# Precision_Dual_Layer.net
KiCad netlist of a schematic drawn in EAGLE
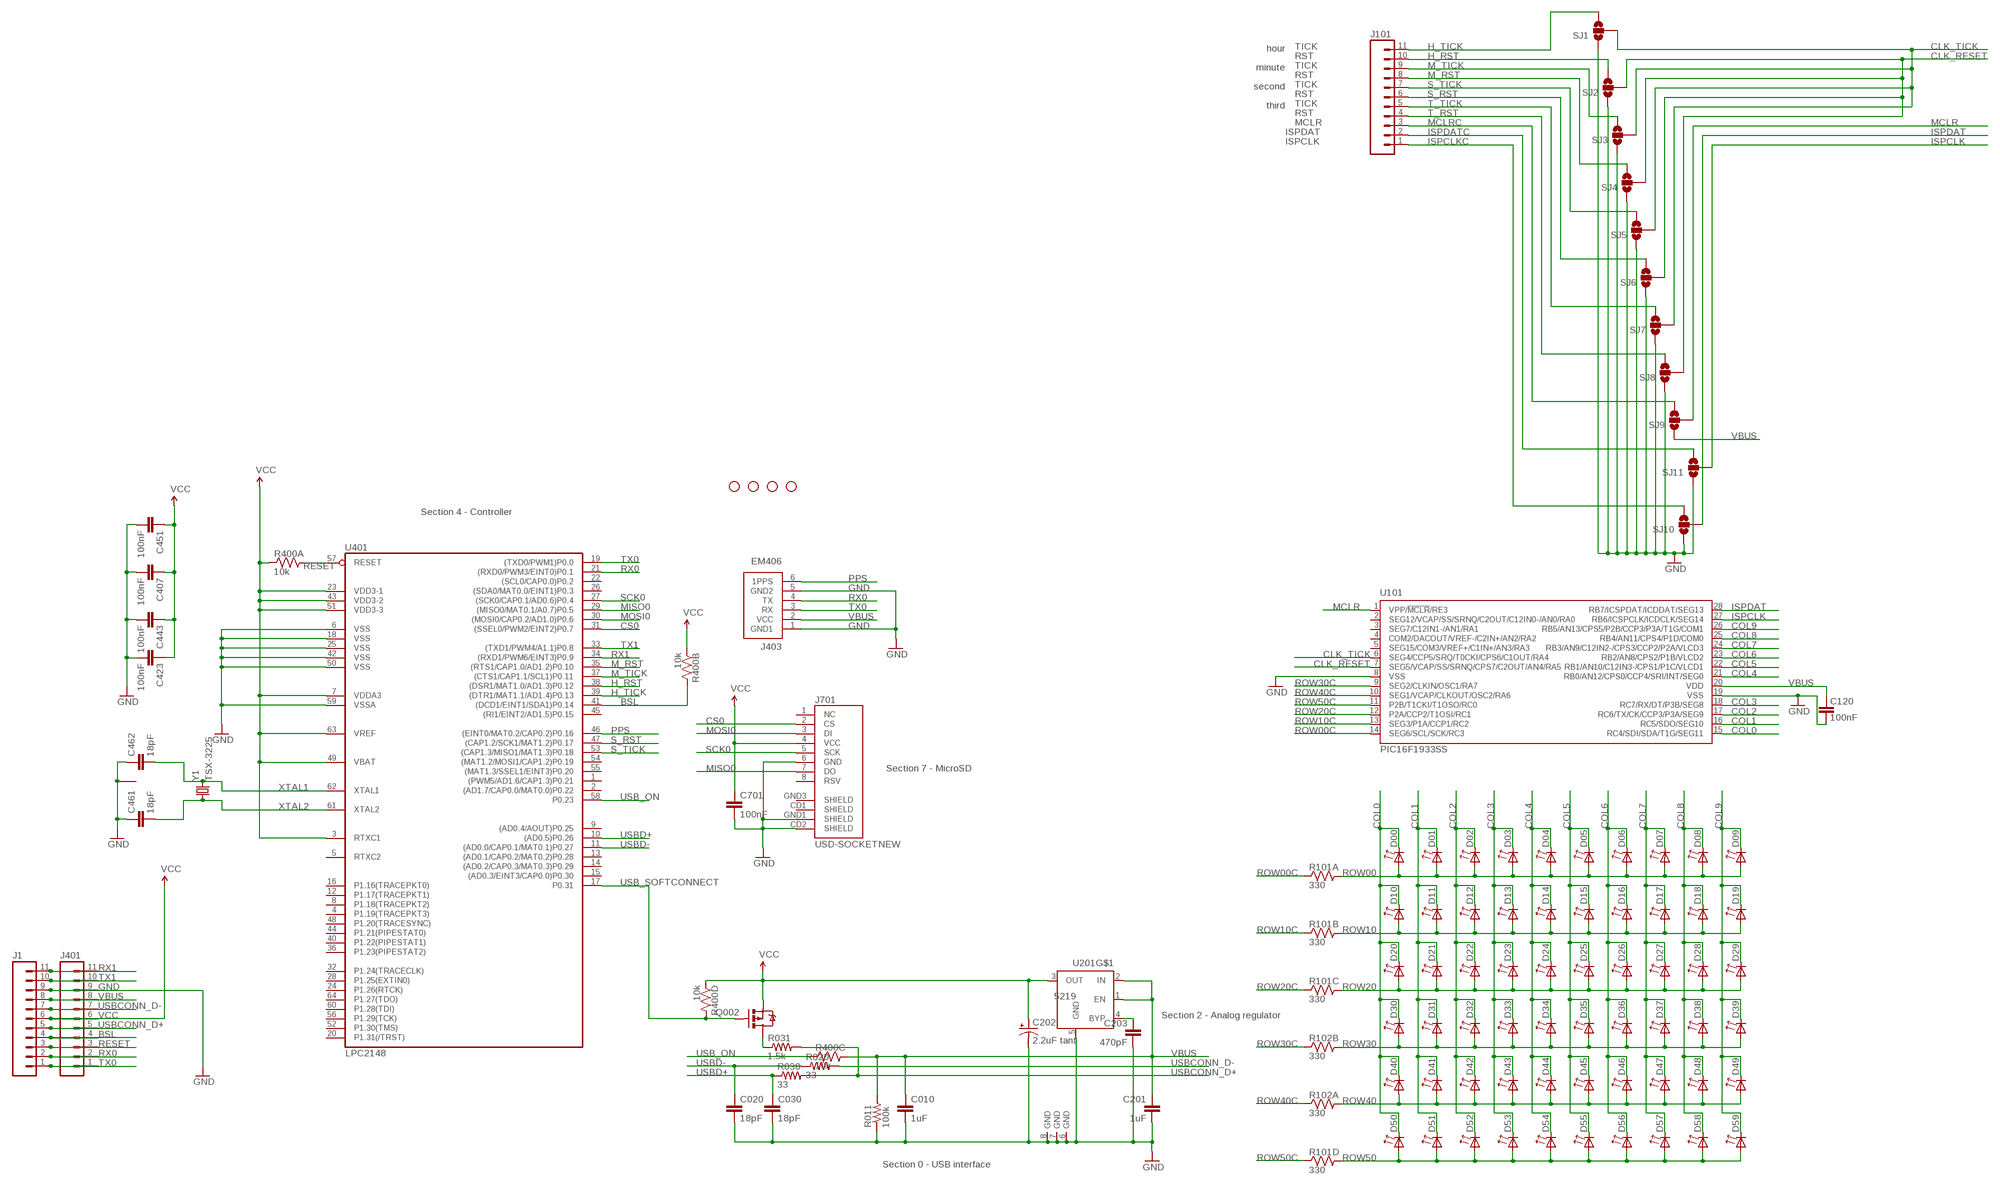
[diagram p0: schematic, sheet 1, part 1 of 2]
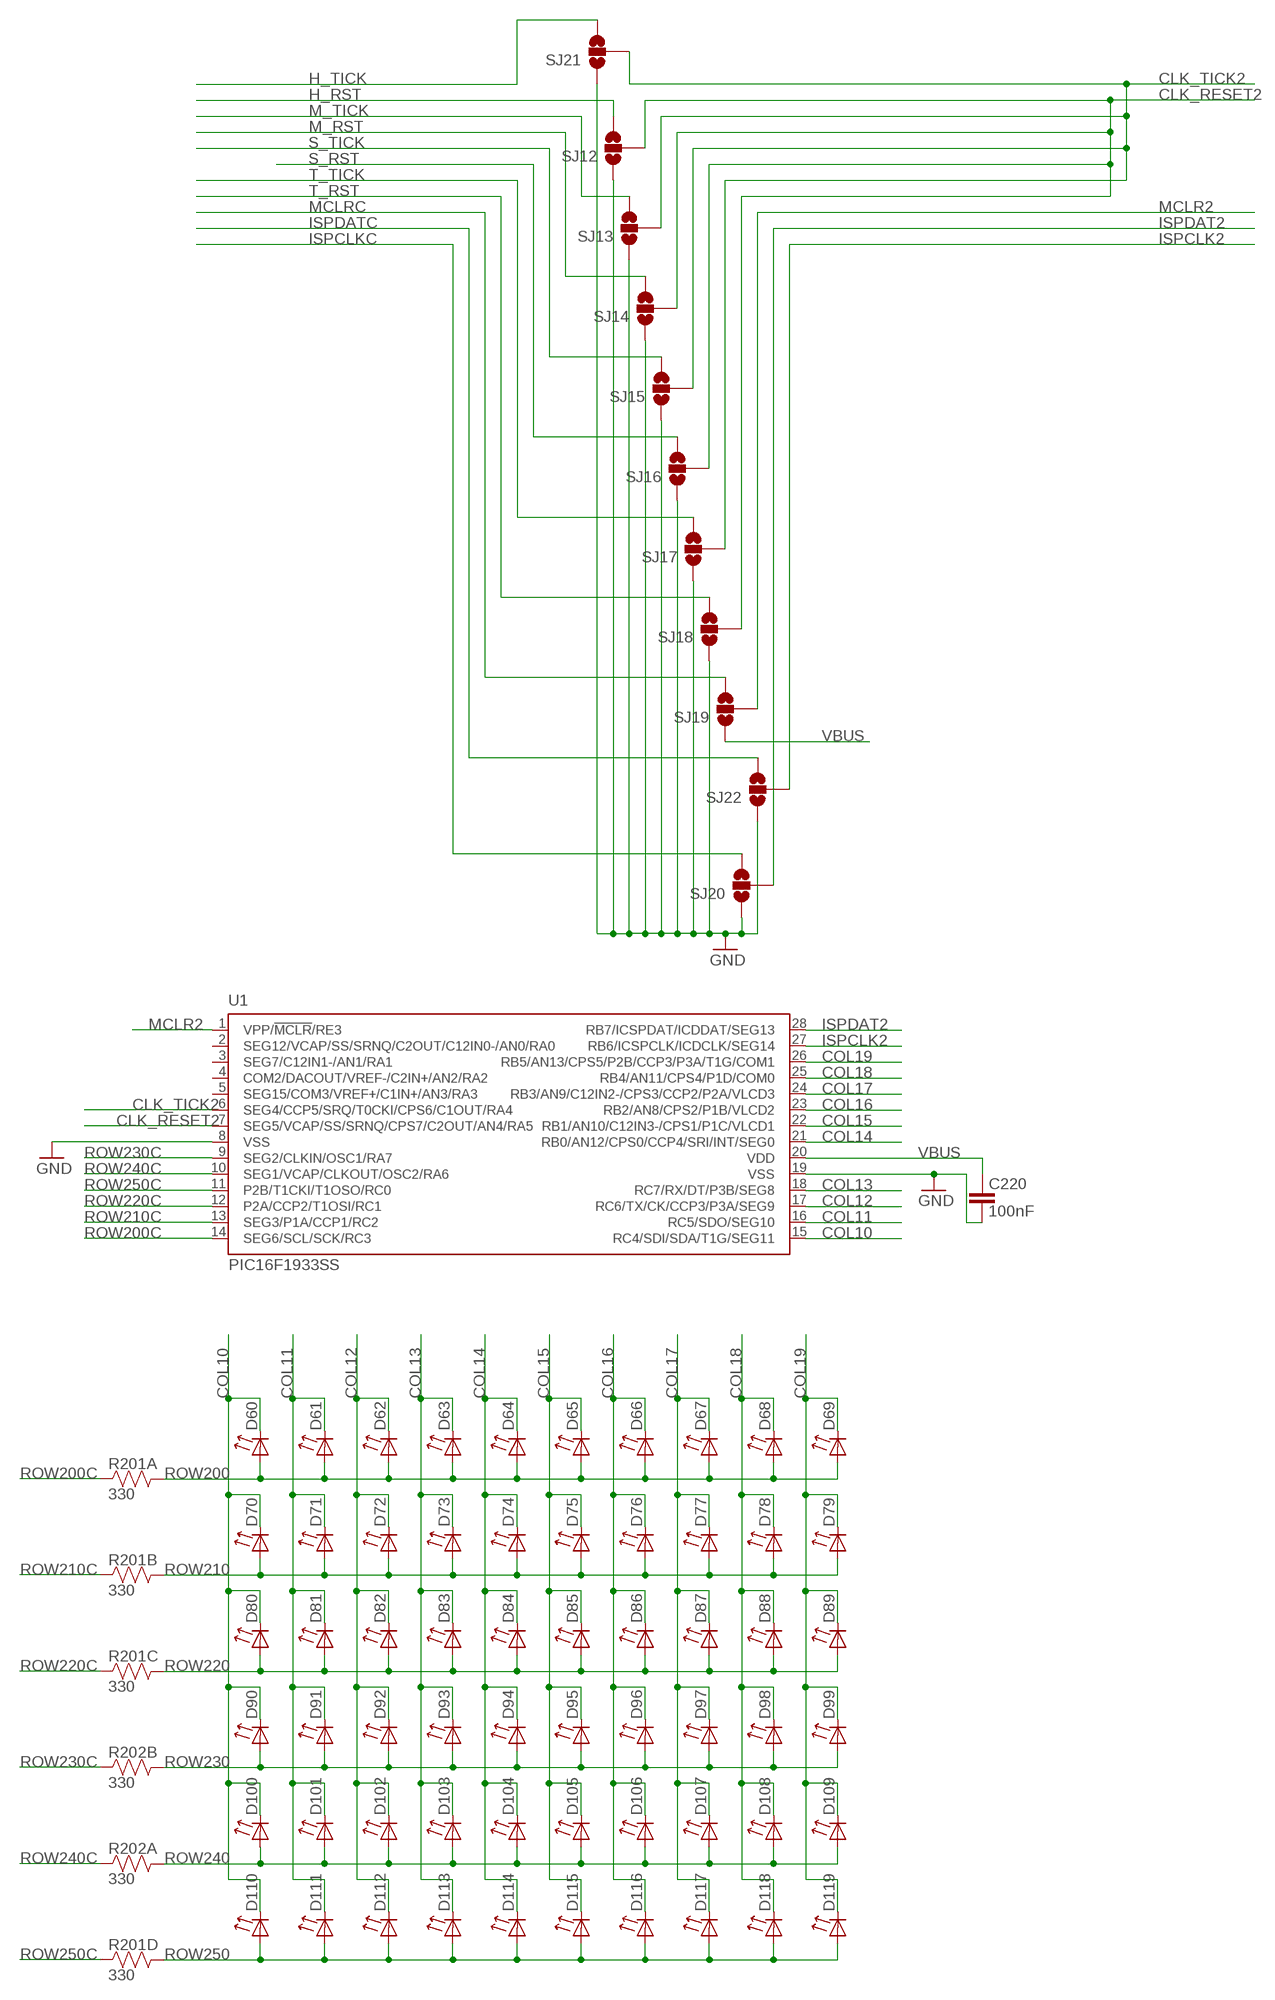
[diagram p1: schematic, sheet 1, part 2 of 2]

(export (version "E")
  (design (tool "Eeschema 10.0.6"))
  (components
    (comp (ref "C010")
      (value "1uF")
      (footprint "eagle-import:0402-CAP")
      (libsource (lib "eagle-import") (part "CAP0402-CAP"))
    )
    (comp (ref "C020")
      (value "18pF")
      (footprint "eagle-import:0402-CAP")
      (libsource (lib "eagle-import") (part "CAP0402-CAP"))
    )
    (comp (ref "C030")
      (value "18pF")
      (footprint "eagle-import:0402-CAP")
      (libsource (lib "eagle-import") (part "CAP0402-CAP"))
    )
    (comp (ref "C120")
      (value "100nF")
      (footprint "eagle-import:0402-CAP")
      (libsource (lib "eagle-import") (part "CAP0402-CAP"))
    )
    (comp (ref "C201")
      (value "1uF")
      (footprint "eagle-import:0402-CAP")
      (libsource (lib "eagle-import") (part "CAP0402-CAP"))
    )
    (comp (ref "C202")
      (value "2.2uF tant")
      (footprint "eagle-import:EIA3216")
      (libsource (lib "eagle-import") (part "CAP_POL1206"))
    )
    (comp (ref "C203")
      (value "470pF")
      (footprint "eagle-import:0402-CAP")
      (libsource (lib "eagle-import") (part "CAP0402-CAP"))
    )
    (comp (ref "C220")
      (value "100nF")
      (footprint "eagle-import:0402-CAP")
      (libsource (lib "eagle-import") (part "CAP0402-CAP"))
    )
    (comp (ref "C407")
      (value "100nF")
      (footprint "eagle-import:0402-CAP")
      (libsource (lib "eagle-import") (part "CAP0402-CAP"))
    )
    (comp (ref "C423")
      (value "100nF")
      (footprint "eagle-import:0402-CAP")
      (libsource (lib "eagle-import") (part "CAP0402-CAP"))
    )
    (comp (ref "C443")
      (value "100nF")
      (footprint "eagle-import:0402-CAP")
      (libsource (lib "eagle-import") (part "CAP0402-CAP"))
    )
    (comp (ref "C451")
      (value "100nF")
      (footprint "eagle-import:0402-CAP")
      (libsource (lib "eagle-import") (part "CAP0402-CAP"))
    )
    (comp (ref "C461")
      (value "18pF")
      (footprint "eagle-import:0402-CAP")
      (libsource (lib "eagle-import") (part "CAP0402-CAP"))
    )
    (comp (ref "C462")
      (value "18pF")
      (footprint "eagle-import:0402-CAP")
      (libsource (lib "eagle-import") (part "CAP0402-CAP"))
    )
    (comp (ref "C701")
      (value "100nF")
      (footprint "eagle-import:0402-CAP")
      (libsource (lib "eagle-import") (part "CAP0402-CAP"))
    )
    (comp (ref "D00")
      (value "LED0603_SIDE")
      (footprint "eagle-import:LED0603_SIDE")
      (libsource (lib "eagle-import") (part "LED0603_SIDE"))
    )
    (comp (ref "D01")
      (value "LED0603_SIDE")
      (footprint "eagle-import:LED0603_SIDE")
      (libsource (lib "eagle-import") (part "LED0603_SIDE"))
    )
    (comp (ref "D02")
      (value "LED0603_SIDE")
      (footprint "eagle-import:LED0603_SIDE")
      (libsource (lib "eagle-import") (part "LED0603_SIDE"))
    )
    (comp (ref "D03")
      (value "LED0603_SIDE")
      (footprint "eagle-import:LED0603_SIDE")
      (libsource (lib "eagle-import") (part "LED0603_SIDE"))
    )
    (comp (ref "D04")
      (value "LED0603_SIDE")
      (footprint "eagle-import:LED0603_SIDE")
      (libsource (lib "eagle-import") (part "LED0603_SIDE"))
    )
    (comp (ref "D05")
      (value "LED0603_SIDE")
      (footprint "eagle-import:LED0603_SIDE")
      (libsource (lib "eagle-import") (part "LED0603_SIDE"))
    )
    (comp (ref "D06")
      (value "LED0603_SIDE")
      (footprint "eagle-import:LED0603_SIDE")
      (libsource (lib "eagle-import") (part "LED0603_SIDE"))
    )
    (comp (ref "D07")
      (value "LED0603_SIDE")
      (footprint "eagle-import:LED0603_SIDE")
      (libsource (lib "eagle-import") (part "LED0603_SIDE"))
    )
    (comp (ref "D08")
      (value "LED0603_SIDE")
      (footprint "eagle-import:LED0603_SIDE")
      (libsource (lib "eagle-import") (part "LED0603_SIDE"))
    )
    (comp (ref "D09")
      (value "LED0603_SIDE")
      (footprint "eagle-import:LED0603_SIDE")
      (libsource (lib "eagle-import") (part "LED0603_SIDE"))
    )
    (comp (ref "D10")
      (value "LED0603_SIDE")
      (footprint "eagle-import:LED0603_SIDE")
      (libsource (lib "eagle-import") (part "LED0603_SIDE"))
    )
    (comp (ref "D11")
      (value "LED0603_SIDE")
      (footprint "eagle-import:LED0603_SIDE")
      (libsource (lib "eagle-import") (part "LED0603_SIDE"))
    )
    (comp (ref "D12")
      (value "LED0603_SIDE")
      (footprint "eagle-import:LED0603_SIDE")
      (libsource (lib "eagle-import") (part "LED0603_SIDE"))
    )
    (comp (ref "D13")
      (value "LED0603_SIDE")
      (footprint "eagle-import:LED0603_SIDE")
      (libsource (lib "eagle-import") (part "LED0603_SIDE"))
    )
    (comp (ref "D14")
      (value "LED0603_SIDE")
      (footprint "eagle-import:LED0603_SIDE")
      (libsource (lib "eagle-import") (part "LED0603_SIDE"))
    )
    (comp (ref "D15")
      (value "LED0603_SIDE")
      (footprint "eagle-import:LED0603_SIDE")
      (libsource (lib "eagle-import") (part "LED0603_SIDE"))
    )
    (comp (ref "D16")
      (value "LED0603_SIDE")
      (footprint "eagle-import:LED0603_SIDE")
      (libsource (lib "eagle-import") (part "LED0603_SIDE"))
    )
    (comp (ref "D17")
      (value "LED0603_SIDE")
      (footprint "eagle-import:LED0603_SIDE")
      (libsource (lib "eagle-import") (part "LED0603_SIDE"))
    )
    (comp (ref "D18")
      (value "LED0603_SIDE")
      (footprint "eagle-import:LED0603_SIDE")
      (libsource (lib "eagle-import") (part "LED0603_SIDE"))
    )
    (comp (ref "D19")
      (value "LED0603_SIDE")
      (footprint "eagle-import:LED0603_SIDE")
      (libsource (lib "eagle-import") (part "LED0603_SIDE"))
    )
    (comp (ref "D20")
      (value "LED0603_SIDE")
      (footprint "eagle-import:LED0603_SIDE")
      (libsource (lib "eagle-import") (part "LED0603_SIDE"))
    )
    (comp (ref "D21")
      (value "LED0603_SIDE")
      (footprint "eagle-import:LED0603_SIDE")
      (libsource (lib "eagle-import") (part "LED0603_SIDE"))
    )
    (comp (ref "D22")
      (value "LED0603_SIDE")
      (footprint "eagle-import:LED0603_SIDE")
      (libsource (lib "eagle-import") (part "LED0603_SIDE"))
    )
    (comp (ref "D23")
      (value "LED0603_SIDE")
      (footprint "eagle-import:LED0603_SIDE")
      (libsource (lib "eagle-import") (part "LED0603_SIDE"))
    )
    (comp (ref "D24")
      (value "LED0603_SIDE")
      (footprint "eagle-import:LED0603_SIDE")
      (libsource (lib "eagle-import") (part "LED0603_SIDE"))
    )
    (comp (ref "D25")
      (value "LED0603_SIDE")
      (footprint "eagle-import:LED0603_SIDE")
      (libsource (lib "eagle-import") (part "LED0603_SIDE"))
    )
    (comp (ref "D26")
      (value "LED0603_SIDE")
      (footprint "eagle-import:LED0603_SIDE")
      (libsource (lib "eagle-import") (part "LED0603_SIDE"))
    )
    (comp (ref "D27")
      (value "LED0603_SIDE")
      (footprint "eagle-import:LED0603_SIDE")
      (libsource (lib "eagle-import") (part "LED0603_SIDE"))
    )
    (comp (ref "D28")
      (value "LED0603_SIDE")
      (footprint "eagle-import:LED0603_SIDE")
      (libsource (lib "eagle-import") (part "LED0603_SIDE"))
    )
    (comp (ref "D29")
      (value "LED0603_SIDE")
      (footprint "eagle-import:LED0603_SIDE")
      (libsource (lib "eagle-import") (part "LED0603_SIDE"))
    )
    (comp (ref "D30")
      (value "LED0603_SIDE")
      (footprint "eagle-import:LED0603_SIDE")
      (libsource (lib "eagle-import") (part "LED0603_SIDE"))
    )
    (comp (ref "D31")
      (value "LED0603_SIDE")
      (footprint "eagle-import:LED0603_SIDE")
      (libsource (lib "eagle-import") (part "LED0603_SIDE"))
    )
    (comp (ref "D32")
      (value "LED0603_SIDE")
      (footprint "eagle-import:LED0603_SIDE")
      (libsource (lib "eagle-import") (part "LED0603_SIDE"))
    )
    (comp (ref "D33")
      (value "LED0603_SIDE")
      (footprint "eagle-import:LED0603_SIDE")
      (libsource (lib "eagle-import") (part "LED0603_SIDE"))
    )
    (comp (ref "D34")
      (value "LED0603_SIDE")
      (footprint "eagle-import:LED0603_SIDE")
      (libsource (lib "eagle-import") (part "LED0603_SIDE"))
    )
    (comp (ref "D35")
      (value "LED0603_SIDE")
      (footprint "eagle-import:LED0603_SIDE")
      (libsource (lib "eagle-import") (part "LED0603_SIDE"))
    )
    (comp (ref "D36")
      (value "LED0603_SIDE")
      (footprint "eagle-import:LED0603_SIDE")
      (libsource (lib "eagle-import") (part "LED0603_SIDE"))
    )
    (comp (ref "D37")
      (value "LED0603_SIDE")
      (footprint "eagle-import:LED0603_SIDE")
      (libsource (lib "eagle-import") (part "LED0603_SIDE"))
    )
    (comp (ref "D38")
      (value "LED0603_SIDE")
      (footprint "eagle-import:LED0603_SIDE")
      (libsource (lib "eagle-import") (part "LED0603_SIDE"))
    )
    (comp (ref "D39")
      (value "LED0603_SIDE")
      (footprint "eagle-import:LED0603_SIDE")
      (libsource (lib "eagle-import") (part "LED0603_SIDE"))
    )
    (comp (ref "D40")
      (value "LED0603_SIDE")
      (footprint "eagle-import:LED0603_SIDE")
      (libsource (lib "eagle-import") (part "LED0603_SIDE"))
    )
    (comp (ref "D41")
      (value "LED0603_SIDE")
      (footprint "eagle-import:LED0603_SIDE")
      (libsource (lib "eagle-import") (part "LED0603_SIDE"))
    )
    (comp (ref "D42")
      (value "LED0603_SIDE")
      (footprint "eagle-import:LED0603_SIDE")
      (libsource (lib "eagle-import") (part "LED0603_SIDE"))
    )
    (comp (ref "D43")
      (value "LED0603_SIDE")
      (footprint "eagle-import:LED0603_SIDE")
      (libsource (lib "eagle-import") (part "LED0603_SIDE"))
    )
    (comp (ref "D44")
      (value "LED0603_SIDE")
      (footprint "eagle-import:LED0603_SIDE")
      (libsource (lib "eagle-import") (part "LED0603_SIDE"))
    )
    (comp (ref "D45")
      (value "LED0603_SIDE")
      (footprint "eagle-import:LED0603_SIDE")
      (libsource (lib "eagle-import") (part "LED0603_SIDE"))
    )
    (comp (ref "D46")
      (value "LED0603_SIDE")
      (footprint "eagle-import:LED0603_SIDE")
      (libsource (lib "eagle-import") (part "LED0603_SIDE"))
    )
    (comp (ref "D47")
      (value "LED0603_SIDE")
      (footprint "eagle-import:LED0603_SIDE")
      (libsource (lib "eagle-import") (part "LED0603_SIDE"))
    )
    (comp (ref "D48")
      (value "LED0603_SIDE")
      (footprint "eagle-import:LED0603_SIDE")
      (libsource (lib "eagle-import") (part "LED0603_SIDE"))
    )
    (comp (ref "D49")
      (value "LED0603_SIDE")
      (footprint "eagle-import:LED0603_SIDE")
      (libsource (lib "eagle-import") (part "LED0603_SIDE"))
    )
    (comp (ref "D50")
      (value "LED0603_SIDE")
      (footprint "eagle-import:LED0603_SIDE")
      (libsource (lib "eagle-import") (part "LED0603_SIDE"))
    )
    (comp (ref "D51")
      (value "LED0603_SIDE")
      (footprint "eagle-import:LED0603_SIDE")
      (libsource (lib "eagle-import") (part "LED0603_SIDE"))
    )
    (comp (ref "D52")
      (value "LED0603_SIDE")
      (footprint "eagle-import:LED0603_SIDE")
      (libsource (lib "eagle-import") (part "LED0603_SIDE"))
    )
    (comp (ref "D53")
      (value "LED0603_SIDE")
      (footprint "eagle-import:LED0603_SIDE")
      (libsource (lib "eagle-import") (part "LED0603_SIDE"))
    )
    (comp (ref "D54")
      (value "LED0603_SIDE")
      (footprint "eagle-import:LED0603_SIDE")
      (libsource (lib "eagle-import") (part "LED0603_SIDE"))
    )
    (comp (ref "D55")
      (value "LED0603_SIDE")
      (footprint "eagle-import:LED0603_SIDE")
      (libsource (lib "eagle-import") (part "LED0603_SIDE"))
    )
    (comp (ref "D56")
      (value "LED0603_SIDE")
      (footprint "eagle-import:LED0603_SIDE")
      (libsource (lib "eagle-import") (part "LED0603_SIDE"))
    )
    (comp (ref "D57")
      (value "LED0603_SIDE")
      (footprint "eagle-import:LED0603_SIDE")
      (libsource (lib "eagle-import") (part "LED0603_SIDE"))
    )
    (comp (ref "D58")
      (value "LED0603_SIDE")
      (footprint "eagle-import:LED0603_SIDE")
      (libsource (lib "eagle-import") (part "LED0603_SIDE"))
    )
    (comp (ref "D59")
      (value "LED0603_SIDE")
      (footprint "eagle-import:LED0603_SIDE")
      (libsource (lib "eagle-import") (part "LED0603_SIDE"))
    )
    (comp (ref "D60")
      (value "LED0603_SIDE")
      (footprint "eagle-import:LED0603_SIDE")
      (libsource (lib "eagle-import") (part "LED0603_SIDE"))
    )
    (comp (ref "D61")
      (value "LED0603_SIDE")
      (footprint "eagle-import:LED0603_SIDE")
      (libsource (lib "eagle-import") (part "LED0603_SIDE"))
    )
    (comp (ref "D62")
      (value "LED0603_SIDE")
      (footprint "eagle-import:LED0603_SIDE")
      (libsource (lib "eagle-import") (part "LED0603_SIDE"))
    )
    (comp (ref "D63")
      (value "LED0603_SIDE")
      (footprint "eagle-import:LED0603_SIDE")
      (libsource (lib "eagle-import") (part "LED0603_SIDE"))
    )
    (comp (ref "D64")
      (value "LED0603_SIDE")
      (footprint "eagle-import:LED0603_SIDE")
      (libsource (lib "eagle-import") (part "LED0603_SIDE"))
    )
    (comp (ref "D65")
      (value "LED0603_SIDE")
      (footprint "eagle-import:LED0603_SIDE")
      (libsource (lib "eagle-import") (part "LED0603_SIDE"))
    )
    (comp (ref "D66")
      (value "LED0603_SIDE")
      (footprint "eagle-import:LED0603_SIDE")
      (libsource (lib "eagle-import") (part "LED0603_SIDE"))
    )
    (comp (ref "D67")
      (value "LED0603_SIDE")
      (footprint "eagle-import:LED0603_SIDE")
      (libsource (lib "eagle-import") (part "LED0603_SIDE"))
    )
    (comp (ref "D68")
      (value "LED0603_SIDE")
      (footprint "eagle-import:LED0603_SIDE")
      (libsource (lib "eagle-import") (part "LED0603_SIDE"))
    )
    (comp (ref "D69")
      (value "LED0603_SIDE")
      (footprint "eagle-import:LED0603_SIDE")
      (libsource (lib "eagle-import") (part "LED0603_SIDE"))
    )
    (comp (ref "D70")
      (value "LED0603_SIDE")
      (footprint "eagle-import:LED0603_SIDE")
      (libsource (lib "eagle-import") (part "LED0603_SIDE"))
    )
    (comp (ref "D71")
      (value "LED0603_SIDE")
      (footprint "eagle-import:LED0603_SIDE")
      (libsource (lib "eagle-import") (part "LED0603_SIDE"))
    )
    (comp (ref "D72")
      (value "LED0603_SIDE")
      (footprint "eagle-import:LED0603_SIDE")
      (libsource (lib "eagle-import") (part "LED0603_SIDE"))
    )
    (comp (ref "D73")
      (value "LED0603_SIDE")
      (footprint "eagle-import:LED0603_SIDE")
      (libsource (lib "eagle-import") (part "LED0603_SIDE"))
    )
    (comp (ref "D74")
      (value "LED0603_SIDE")
      (footprint "eagle-import:LED0603_SIDE")
      (libsource (lib "eagle-import") (part "LED0603_SIDE"))
    )
    (comp (ref "D75")
      (value "LED0603_SIDE")
      (footprint "eagle-import:LED0603_SIDE")
      (libsource (lib "eagle-import") (part "LED0603_SIDE"))
    )
    (comp (ref "D76")
      (value "LED0603_SIDE")
      (footprint "eagle-import:LED0603_SIDE")
      (libsource (lib "eagle-import") (part "LED0603_SIDE"))
    )
    (comp (ref "D77")
      (value "LED0603_SIDE")
      (footprint "eagle-import:LED0603_SIDE")
      (libsource (lib "eagle-import") (part "LED0603_SIDE"))
    )
    (comp (ref "D78")
      (value "LED0603_SIDE")
      (footprint "eagle-import:LED0603_SIDE")
      (libsource (lib "eagle-import") (part "LED0603_SIDE"))
    )
    (comp (ref "D79")
      (value "LED0603_SIDE")
      (footprint "eagle-import:LED0603_SIDE")
      (libsource (lib "eagle-import") (part "LED0603_SIDE"))
    )
    (comp (ref "D80")
      (value "LED0603_SIDE")
      (footprint "eagle-import:LED0603_SIDE")
      (libsource (lib "eagle-import") (part "LED0603_SIDE"))
    )
    (comp (ref "D81")
      (value "LED0603_SIDE")
      (footprint "eagle-import:LED0603_SIDE")
      (libsource (lib "eagle-import") (part "LED0603_SIDE"))
    )
    (comp (ref "D82")
      (value "LED0603_SIDE")
      (footprint "eagle-import:LED0603_SIDE")
      (libsource (lib "eagle-import") (part "LED0603_SIDE"))
    )
    (comp (ref "D83")
      (value "LED0603_SIDE")
      (footprint "eagle-import:LED0603_SIDE")
      (libsource (lib "eagle-import") (part "LED0603_SIDE"))
    )
    (comp (ref "D84")
      (value "LED0603_SIDE")
      (footprint "eagle-import:LED0603_SIDE")
      (libsource (lib "eagle-import") (part "LED0603_SIDE"))
    )
    (comp (ref "D85")
      (value "LED0603_SIDE")
      (footprint "eagle-import:LED0603_SIDE")
      (libsource (lib "eagle-import") (part "LED0603_SIDE"))
    )
    (comp (ref "D86")
      (value "LED0603_SIDE")
      (footprint "eagle-import:LED0603_SIDE")
      (libsource (lib "eagle-import") (part "LED0603_SIDE"))
    )
    (comp (ref "D87")
      (value "LED0603_SIDE")
      (footprint "eagle-import:LED0603_SIDE")
      (libsource (lib "eagle-import") (part "LED0603_SIDE"))
    )
    (comp (ref "D88")
      (value "LED0603_SIDE")
      (footprint "eagle-import:LED0603_SIDE")
      (libsource (lib "eagle-import") (part "LED0603_SIDE"))
    )
    (comp (ref "D89")
      (value "LED0603_SIDE")
      (footprint "eagle-import:LED0603_SIDE")
      (libsource (lib "eagle-import") (part "LED0603_SIDE"))
    )
    (comp (ref "D90")
      (value "LED0603_SIDE")
      (footprint "eagle-import:LED0603_SIDE")
      (libsource (lib "eagle-import") (part "LED0603_SIDE"))
    )
    (comp (ref "D91")
      (value "LED0603_SIDE")
      (footprint "eagle-import:LED0603_SIDE")
      (libsource (lib "eagle-import") (part "LED0603_SIDE"))
    )
    (comp (ref "D92")
      (value "LED0603_SIDE")
      (footprint "eagle-import:LED0603_SIDE")
      (libsource (lib "eagle-import") (part "LED0603_SIDE"))
    )
    (comp (ref "D93")
      (value "LED0603_SIDE")
      (footprint "eagle-import:LED0603_SIDE")
      (libsource (lib "eagle-import") (part "LED0603_SIDE"))
    )
    (comp (ref "D94")
      (value "LED0603_SIDE")
      (footprint "eagle-import:LED0603_SIDE")
      (libsource (lib "eagle-import") (part "LED0603_SIDE"))
    )
    (comp (ref "D95")
      (value "LED0603_SIDE")
      (footprint "eagle-import:LED0603_SIDE")
      (libsource (lib "eagle-import") (part "LED0603_SIDE"))
    )
    (comp (ref "D96")
      (value "LED0603_SIDE")
      (footprint "eagle-import:LED0603_SIDE")
      (libsource (lib "eagle-import") (part "LED0603_SIDE"))
    )
    (comp (ref "D97")
      (value "LED0603_SIDE")
      (footprint "eagle-import:LED0603_SIDE")
      (libsource (lib "eagle-import") (part "LED0603_SIDE"))
    )
    (comp (ref "D98")
      (value "LED0603_SIDE")
      (footprint "eagle-import:LED0603_SIDE")
      (libsource (lib "eagle-import") (part "LED0603_SIDE"))
    )
    (comp (ref "D99")
      (value "LED0603_SIDE")
      (footprint "eagle-import:LED0603_SIDE")
      (libsource (lib "eagle-import") (part "LED0603_SIDE"))
    )
    (comp (ref "D100")
      (value "LED0603_SIDE")
      (footprint "eagle-import:LED0603_SIDE")
      (libsource (lib "eagle-import") (part "LED0603_SIDE"))
    )
    (comp (ref "D101")
      (value "LED0603_SIDE")
      (footprint "eagle-import:LED0603_SIDE")
      (libsource (lib "eagle-import") (part "LED0603_SIDE"))
    )
    (comp (ref "D102")
      (value "LED0603_SIDE")
      (footprint "eagle-import:LED0603_SIDE")
      (libsource (lib "eagle-import") (part "LED0603_SIDE"))
    )
    (comp (ref "D103")
      (value "LED0603_SIDE")
      (footprint "eagle-import:LED0603_SIDE")
      (libsource (lib "eagle-import") (part "LED0603_SIDE"))
    )
    (comp (ref "D104")
      (value "LED0603_SIDE")
      (footprint "eagle-import:LED0603_SIDE")
      (libsource (lib "eagle-import") (part "LED0603_SIDE"))
    )
    (comp (ref "D105")
      (value "LED0603_SIDE")
      (footprint "eagle-import:LED0603_SIDE")
      (libsource (lib "eagle-import") (part "LED0603_SIDE"))
    )
    (comp (ref "D106")
      (value "LED0603_SIDE")
      (footprint "eagle-import:LED0603_SIDE")
      (libsource (lib "eagle-import") (part "LED0603_SIDE"))
    )
    (comp (ref "D107")
      (value "LED0603_SIDE")
      (footprint "eagle-import:LED0603_SIDE")
      (libsource (lib "eagle-import") (part "LED0603_SIDE"))
    )
    (comp (ref "D108")
      (value "LED0603_SIDE")
      (footprint "eagle-import:LED0603_SIDE")
      (libsource (lib "eagle-import") (part "LED0603_SIDE"))
    )
    (comp (ref "D109")
      (value "LED0603_SIDE")
      (footprint "eagle-import:LED0603_SIDE")
      (libsource (lib "eagle-import") (part "LED0603_SIDE"))
    )
    (comp (ref "D110")
      (value "LED0603_SIDE")
      (footprint "eagle-import:LED0603_SIDE")
      (libsource (lib "eagle-import") (part "LED0603_SIDE"))
    )
    (comp (ref "D111")
      (value "LED0603_SIDE")
      (footprint "eagle-import:LED0603_SIDE")
      (libsource (lib "eagle-import") (part "LED0603_SIDE"))
    )
    (comp (ref "D112")
      (value "LED0603_SIDE")
      (footprint "eagle-import:LED0603_SIDE")
      (libsource (lib "eagle-import") (part "LED0603_SIDE"))
    )
    (comp (ref "D113")
      (value "LED0603_SIDE")
      (footprint "eagle-import:LED0603_SIDE")
      (libsource (lib "eagle-import") (part "LED0603_SIDE"))
    )
    (comp (ref "D114")
      (value "LED0603_SIDE")
      (footprint "eagle-import:LED0603_SIDE")
      (libsource (lib "eagle-import") (part "LED0603_SIDE"))
    )
    (comp (ref "D115")
      (value "LED0603_SIDE")
      (footprint "eagle-import:LED0603_SIDE")
      (libsource (lib "eagle-import") (part "LED0603_SIDE"))
    )
    (comp (ref "D116")
      (value "LED0603_SIDE")
      (footprint "eagle-import:LED0603_SIDE")
      (libsource (lib "eagle-import") (part "LED0603_SIDE"))
    )
    (comp (ref "D117")
      (value "LED0603_SIDE")
      (footprint "eagle-import:LED0603_SIDE")
      (libsource (lib "eagle-import") (part "LED0603_SIDE"))
    )
    (comp (ref "D118")
      (value "LED0603_SIDE")
      (footprint "eagle-import:LED0603_SIDE")
      (libsource (lib "eagle-import") (part "LED0603_SIDE"))
    )
    (comp (ref "D119")
      (value "LED0603_SIDE")
      (footprint "eagle-import:LED0603_SIDE")
      (libsource (lib "eagle-import") (part "LED0603_SIDE"))
    )
    (comp (ref "J1")
      (value "M11PTH")
      (footprint "eagle-import:1X11")
      (libsource (lib "eagle-import") (part "M11PTH"))
    )
    (comp (ref "J101")
      (value "M11PTH")
      (footprint "eagle-import:1X11")
      (libsource (lib "eagle-import") (part "M11PTH"))
    )
    (comp (ref "J401")
      (value "M11PTH")
      (footprint "eagle-import:1X11")
      (libsource (lib "eagle-import") (part "M11PTH"))
    )
    (comp (ref "J403")
      (value "EM406")
      (footprint "eagle-import:EM406@1")
      (libsource (lib "eagle-import") (part "EM406"))
    )
    (comp (ref "J701")
      (value "USD-SOCKETNEW")
      (footprint "eagle-import:MICRO-SD-SOCKET-PP")
      (libsource (lib "eagle-import") (part "USD-SOCKETNEW"))
    )
    (comp (ref "JP3")
      (value "STAND-OFF")
      (footprint "eagle-import:STAND-OFF")
      (libsource (lib "eagle-import") (part "STAND-OFF"))
    )
    (comp (ref "JP4")
      (value "STAND-OFF")
      (footprint "eagle-import:STAND-OFF")
      (libsource (lib "eagle-import") (part "STAND-OFF"))
    )
    (comp (ref "JP5")
      (value "STAND-OFF")
      (footprint "eagle-import:STAND-OFF")
      (libsource (lib "eagle-import") (part "STAND-OFF"))
    )
    (comp (ref "JP6")
      (value "STAND-OFF")
      (footprint "eagle-import:STAND-OFF")
      (libsource (lib "eagle-import") (part "STAND-OFF"))
    )
    (comp (ref "Q002")
      (value "PMOS")
      (footprint "eagle-import:SOT23-3")
      (libsource (lib "eagle-import") (part "MOSFET-PCHANNELSMD"))
    )
    (comp (ref "R011")
      (value "100k")
      (footprint "eagle-import:0402-RES")
      (libsource (lib "eagle-import") (part "RESISTOR0402-RES"))
    )
    (comp (ref "R020")
      (value "33")
      (footprint "eagle-import:0402-RES")
      (libsource (lib "eagle-import") (part "RESISTOR0402-RES"))
    )
    (comp (ref "R030")
      (value "33")
      (footprint "eagle-import:0402-RES")
      (libsource (lib "eagle-import") (part "RESISTOR0402-RES"))
    )
    (comp (ref "R031")
      (value "1.5k")
      (footprint "eagle-import:0402-RES")
      (libsource (lib "eagle-import") (part "RESISTOR0402-RES"))
    )
    (comp (ref "R101")
      (value "330")
      (footprint "eagle-import:CRA04")
      (libsource (lib "eagle-import") (part "RP404"))
    )
    (comp (ref "R102")
      (value "330")
      (footprint "eagle-import:CRA04")
      (libsource (lib "eagle-import") (part "RP404"))
    )
    (comp (ref "R201")
      (value "330")
      (footprint "eagle-import:CRA04")
      (libsource (lib "eagle-import") (part "RP404"))
    )
    (comp (ref "R202")
      (value "330")
      (footprint "eagle-import:CRA04")
      (libsource (lib "eagle-import") (part "RP404"))
    )
    (comp (ref "R400")
      (value "10k")
      (footprint "eagle-import:CRA04")
      (libsource (lib "eagle-import") (part "RP404"))
    )
    (comp (ref "SJ1")
      (value "SOLDERJUMPER_2WAYS")
      (footprint "eagle-import:SJ_3")
      (libsource (lib "eagle-import") (part "SOLDERJUMPER_2WAYS"))
    )
    (comp (ref "SJ2")
      (value "SOLDERJUMPER_2WAYS")
      (footprint "eagle-import:SJ_3")
      (libsource (lib "eagle-import") (part "SOLDERJUMPER_2WAYS"))
    )
    (comp (ref "SJ3")
      (value "SOLDERJUMPER_2WAYS")
      (footprint "eagle-import:SJ_3")
      (libsource (lib "eagle-import") (part "SOLDERJUMPER_2WAYS"))
    )
    (comp (ref "SJ4")
      (value "SOLDERJUMPER_2WAYS")
      (footprint "eagle-import:SJ_3")
      (libsource (lib "eagle-import") (part "SOLDERJUMPER_2WAYS"))
    )
    (comp (ref "SJ5")
      (value "SOLDERJUMPER_2WAYS")
      (footprint "eagle-import:SJ_3")
      (libsource (lib "eagle-import") (part "SOLDERJUMPER_2WAYS"))
    )
    (comp (ref "SJ6")
      (value "SOLDERJUMPER_2WAYS")
      (footprint "eagle-import:SJ_3")
      (libsource (lib "eagle-import") (part "SOLDERJUMPER_2WAYS"))
    )
    (comp (ref "SJ7")
      (value "SOLDERJUMPER_2WAYS")
      (footprint "eagle-import:SJ_3")
      (libsource (lib "eagle-import") (part "SOLDERJUMPER_2WAYS"))
    )
    (comp (ref "SJ8")
      (value "SOLDERJUMPER_2WAYS")
      (footprint "eagle-import:SJ_3")
      (libsource (lib "eagle-import") (part "SOLDERJUMPER_2WAYS"))
    )
    (comp (ref "SJ9")
      (value "SOLDERJUMPER_2WAYS")
      (footprint "eagle-import:SJ_3")
      (libsource (lib "eagle-import") (part "SOLDERJUMPER_2WAYS"))
    )
    (comp (ref "SJ10")
      (value "SOLDERJUMPER_2WAYS")
      (footprint "eagle-import:SJ_3")
      (libsource (lib "eagle-import") (part "SOLDERJUMPER_2WAYS"))
    )
    (comp (ref "SJ11")
      (value "SOLDERJUMPER_2WAYS")
      (footprint "eagle-import:SJ_3")
      (libsource (lib "eagle-import") (part "SOLDERJUMPER_2WAYS"))
    )
    (comp (ref "SJ12")
      (value "SOLDERJUMPER_2WAYS")
      (footprint "eagle-import:SJ_3")
      (libsource (lib "eagle-import") (part "SOLDERJUMPER_2WAYS"))
    )
    (comp (ref "SJ13")
      (value "SOLDERJUMPER_2WAYS")
      (footprint "eagle-import:SJ_3")
      (libsource (lib "eagle-import") (part "SOLDERJUMPER_2WAYS"))
    )
    (comp (ref "SJ14")
      (value "SOLDERJUMPER_2WAYS")
      (footprint "eagle-import:SJ_3")
      (libsource (lib "eagle-import") (part "SOLDERJUMPER_2WAYS"))
    )
    (comp (ref "SJ15")
      (value "SOLDERJUMPER_2WAYS")
      (footprint "eagle-import:SJ_3")
      (libsource (lib "eagle-import") (part "SOLDERJUMPER_2WAYS"))
    )
    (comp (ref "SJ16")
      (value "SOLDERJUMPER_2WAYS")
      (footprint "eagle-import:SJ_3")
      (libsource (lib "eagle-import") (part "SOLDERJUMPER_2WAYS"))
    )
    (comp (ref "SJ17")
      (value "SOLDERJUMPER_2WAYS")
      (footprint "eagle-import:SJ_3")
      (libsource (lib "eagle-import") (part "SOLDERJUMPER_2WAYS"))
    )
    (comp (ref "SJ18")
      (value "SOLDERJUMPER_2WAYS")
      (footprint "eagle-import:SJ_3")
      (libsource (lib "eagle-import") (part "SOLDERJUMPER_2WAYS"))
    )
    (comp (ref "SJ19")
      (value "SOLDERJUMPER_2WAYS")
      (footprint "eagle-import:SJ_3")
      (libsource (lib "eagle-import") (part "SOLDERJUMPER_2WAYS"))
    )
    (comp (ref "SJ20")
      (value "SOLDERJUMPER_2WAYS")
      (footprint "eagle-import:SJ_3")
      (libsource (lib "eagle-import") (part "SOLDERJUMPER_2WAYS"))
    )
    (comp (ref "SJ21")
      (value "SOLDERJUMPER_2WAYS")
      (footprint "eagle-import:SJ_3")
      (libsource (lib "eagle-import") (part "SOLDERJUMPER_2WAYS"))
    )
    (comp (ref "SJ22")
      (value "SOLDERJUMPER_2WAYS")
      (footprint "eagle-import:SJ_3")
      (libsource (lib "eagle-import") (part "SOLDERJUMPER_2WAYS"))
    )
    (comp (ref "U1")
      (value "PIC16F1933SS")
      (footprint "eagle-import:SSOP28")
      (fields (field (name "MPN") "PIC16F1933T-I/SS"))
      (libsource (lib "eagle-import") (part "PIC16F19SS33"))
    )
    (comp (ref "U101")
      (value "PIC16F1933SS")
      (footprint "eagle-import:SSOP28")
      (fields (field (name "MPN") "PIC16F1933T-I/SS"))
      (libsource (lib "eagle-import") (part "PIC16F19SS33"))
    )
    (comp (ref "U201")
      (value "5219")
      (footprint "eagle-import:MSOP08")
      (libsource (lib "eagle-import") (part "MIC5219FMM"))
    )
    (comp (ref "U401")
      (value "LPC2148")
      (footprint "eagle-import:SQFP-S-10X10-64")
      (libsource (lib "eagle-import") (part "LPC213X"))
    )
    (comp (ref "Y1")
      (value "TSX-3225")
      (footprint "eagle-import:CRYSTAL_SMD")
      (libsource (lib "eagle-import") (part "TSX-3225"))
    )
  )
  (nets
    (net (code "1") (name "/BSL") (class "Default")
      (node (ref "J1") (pin "4") (pinfunction "4_4") (pintype "passive"))
      (node (ref "J401") (pin "4") (pinfunction "4_4") (pintype "passive"))
      (node (ref "R400") (pin "7") (pinfunction "2_7") (pintype "passive"))
      (node (ref "U401") (pin "41") (pinfunction "(DCD1/EINT1/SDA1)P0.14_41") (pintype "bidirectional"))
    )
    (net (code "2") (name "/CLK_RESET") (class "Default")
      (node (ref "SJ2") (pin "2") (pinfunction "2_2") (pintype "passive"))
      (node (ref "SJ4") (pin "2") (pinfunction "2_2") (pintype "passive"))
      (node (ref "SJ6") (pin "2") (pinfunction "2_2") (pintype "passive"))
      (node (ref "SJ8") (pin "2") (pinfunction "2_2") (pintype "passive"))
      (node (ref "U101") (pin "7") (pinfunction "SEG5/VCAP/SS/SRNQ/CPS7/C2OUT/AN4/RA5_7") (pintype "bidirectional"))
    )
    (net (code "3") (name "/CLK_RESET2") (class "Default")
      (node (ref "SJ12") (pin "2") (pinfunction "2_2") (pintype "passive"))
      (node (ref "SJ14") (pin "2") (pinfunction "2_2") (pintype "passive"))
      (node (ref "SJ16") (pin "2") (pinfunction "2_2") (pintype "passive"))
      (node (ref "SJ18") (pin "2") (pinfunction "2_2") (pintype "passive"))
      (node (ref "U1") (pin "7") (pinfunction "SEG5/VCAP/SS/SRNQ/CPS7/C2OUT/AN4/RA5_7") (pintype "bidirectional"))
    )
    (net (code "4") (name "/CLK_TICK") (class "Default")
      (node (ref "SJ1") (pin "2") (pinfunction "2_2") (pintype "passive"))
      (node (ref "SJ3") (pin "2") (pinfunction "2_2") (pintype "passive"))
      (node (ref "SJ5") (pin "2") (pinfunction "2_2") (pintype "passive"))
      (node (ref "SJ7") (pin "2") (pinfunction "2_2") (pintype "passive"))
      (node (ref "U101") (pin "6") (pinfunction "SEG4/CCP5/SRQ/T0CKI/CPS6/C1OUT/RA4_6") (pintype "bidirectional"))
    )
    (net (code "5") (name "/CLK_TICK2") (class "Default")
      (node (ref "SJ13") (pin "2") (pinfunction "2_2") (pintype "passive"))
      (node (ref "SJ15") (pin "2") (pinfunction "2_2") (pintype "passive"))
      (node (ref "SJ17") (pin "2") (pinfunction "2_2") (pintype "passive"))
      (node (ref "SJ21") (pin "2") (pinfunction "2_2") (pintype "passive"))
      (node (ref "U1") (pin "6") (pinfunction "SEG4/CCP5/SRQ/T0CKI/CPS6/C1OUT/RA4_6") (pintype "bidirectional"))
    )
    (net (code "6") (name "/COL0") (class "Default")
      (node (ref "D00") (pin "C") (pinfunction "C_C") (pintype "passive"))
      (node (ref "D10") (pin "C") (pinfunction "C_C") (pintype "passive"))
      (node (ref "D20") (pin "C") (pinfunction "C_C") (pintype "passive"))
      (node (ref "D30") (pin "C") (pinfunction "C_C") (pintype "passive"))
      (node (ref "D40") (pin "C") (pinfunction "C_C") (pintype "passive"))
      (node (ref "D50") (pin "C") (pinfunction "C_C") (pintype "passive"))
      (node (ref "U101") (pin "15") (pinfunction "RC4/SDI/SDA/T1G/SEG11_15") (pintype "bidirectional"))
    )
    (net (code "7") (name "/COL1") (class "Default")
      (node (ref "D01") (pin "C") (pinfunction "C_C") (pintype "passive"))
      (node (ref "D11") (pin "C") (pinfunction "C_C") (pintype "passive"))
      (node (ref "D21") (pin "C") (pinfunction "C_C") (pintype "passive"))
      (node (ref "D31") (pin "C") (pinfunction "C_C") (pintype "passive"))
      (node (ref "D41") (pin "C") (pinfunction "C_C") (pintype "passive"))
      (node (ref "D51") (pin "C") (pinfunction "C_C") (pintype "passive"))
      (node (ref "U101") (pin "16") (pinfunction "RC5/SDO/SEG10_16") (pintype "bidirectional"))
    )
    (net (code "8") (name "/COL2") (class "Default")
      (node (ref "D02") (pin "C") (pinfunction "C_C") (pintype "passive"))
      (node (ref "D12") (pin "C") (pinfunction "C_C") (pintype "passive"))
      (node (ref "D22") (pin "C") (pinfunction "C_C") (pintype "passive"))
      (node (ref "D32") (pin "C") (pinfunction "C_C") (pintype "passive"))
      (node (ref "D42") (pin "C") (pinfunction "C_C") (pintype "passive"))
      (node (ref "D52") (pin "C") (pinfunction "C_C") (pintype "passive"))
      (node (ref "U101") (pin "17") (pinfunction "RC6/TX/CK/CCP3/P3A/SEG9_17") (pintype "bidirectional"))
    )
    (net (code "9") (name "/COL3") (class "Default")
      (node (ref "D03") (pin "C") (pinfunction "C_C") (pintype "passive"))
      (node (ref "D13") (pin "C") (pinfunction "C_C") (pintype "passive"))
      (node (ref "D23") (pin "C") (pinfunction "C_C") (pintype "passive"))
      (node (ref "D33") (pin "C") (pinfunction "C_C") (pintype "passive"))
      (node (ref "D43") (pin "C") (pinfunction "C_C") (pintype "passive"))
      (node (ref "D53") (pin "C") (pinfunction "C_C") (pintype "passive"))
      (node (ref "U101") (pin "18") (pinfunction "RC7/RX/DT/P3B/SEG8_18") (pintype "bidirectional"))
    )
    (net (code "10") (name "/COL4") (class "Default")
      (node (ref "D04") (pin "C") (pinfunction "C_C") (pintype "passive"))
      (node (ref "D14") (pin "C") (pinfunction "C_C") (pintype "passive"))
      (node (ref "D24") (pin "C") (pinfunction "C_C") (pintype "passive"))
      (node (ref "D34") (pin "C") (pinfunction "C_C") (pintype "passive"))
      (node (ref "D44") (pin "C") (pinfunction "C_C") (pintype "passive"))
      (node (ref "D54") (pin "C") (pinfunction "C_C") (pintype "passive"))
      (node (ref "U101") (pin "21") (pinfunction "RB0/AN12/CPS0/CCP4/SRI/INT/SEG0_21") (pintype "bidirectional"))
    )
    (net (code "11") (name "/COL5") (class "Default")
      (node (ref "D05") (pin "C") (pinfunction "C_C") (pintype "passive"))
      (node (ref "D15") (pin "C") (pinfunction "C_C") (pintype "passive"))
      (node (ref "D25") (pin "C") (pinfunction "C_C") (pintype "passive"))
      (node (ref "D35") (pin "C") (pinfunction "C_C") (pintype "passive"))
      (node (ref "D45") (pin "C") (pinfunction "C_C") (pintype "passive"))
      (node (ref "D55") (pin "C") (pinfunction "C_C") (pintype "passive"))
      (node (ref "U101") (pin "22") (pinfunction "RB1/AN10/C12IN3-/CPS1/P1C/VLCD1_22") (pintype "bidirectional"))
    )
    (net (code "12") (name "/COL6") (class "Default")
      (node (ref "D06") (pin "C") (pinfunction "C_C") (pintype "passive"))
      (node (ref "D16") (pin "C") (pinfunction "C_C") (pintype "passive"))
      (node (ref "D26") (pin "C") (pinfunction "C_C") (pintype "passive"))
      (node (ref "D36") (pin "C") (pinfunction "C_C") (pintype "passive"))
      (node (ref "D46") (pin "C") (pinfunction "C_C") (pintype "passive"))
      (node (ref "D56") (pin "C") (pinfunction "C_C") (pintype "passive"))
      (node (ref "U101") (pin "23") (pinfunction "RB2/AN8/CPS2/P1B/VLCD2_23") (pintype "bidirectional"))
    )
    (net (code "13") (name "/COL7") (class "Default")
      (node (ref "D07") (pin "C") (pinfunction "C_C") (pintype "passive"))
      (node (ref "D17") (pin "C") (pinfunction "C_C") (pintype "passive"))
      (node (ref "D27") (pin "C") (pinfunction "C_C") (pintype "passive"))
      (node (ref "D37") (pin "C") (pinfunction "C_C") (pintype "passive"))
      (node (ref "D47") (pin "C") (pinfunction "C_C") (pintype "passive"))
      (node (ref "D57") (pin "C") (pinfunction "C_C") (pintype "passive"))
      (node (ref "U101") (pin "24") (pinfunction "RB3/AN9/C12IN2-/CPS3/CCP2/P2A/VLCD3_24") (pintype "bidirectional"))
    )
    (net (code "14") (name "/COL8") (class "Default")
      (node (ref "D08") (pin "C") (pinfunction "C_C") (pintype "passive"))
      (node (ref "D18") (pin "C") (pinfunction "C_C") (pintype "passive"))
      (node (ref "D28") (pin "C") (pinfunction "C_C") (pintype "passive"))
      (node (ref "D38") (pin "C") (pinfunction "C_C") (pintype "passive"))
      (node (ref "D48") (pin "C") (pinfunction "C_C") (pintype "passive"))
      (node (ref "D58") (pin "C") (pinfunction "C_C") (pintype "passive"))
      (node (ref "U101") (pin "25") (pinfunction "RB4/AN11/CPS4/P1D/COM0_25") (pintype "bidirectional"))
    )
    (net (code "15") (name "/COL9") (class "Default")
      (node (ref "D09") (pin "C") (pinfunction "C_C") (pintype "passive"))
      (node (ref "D19") (pin "C") (pinfunction "C_C") (pintype "passive"))
      (node (ref "D29") (pin "C") (pinfunction "C_C") (pintype "passive"))
      (node (ref "D39") (pin "C") (pinfunction "C_C") (pintype "passive"))
      (node (ref "D49") (pin "C") (pinfunction "C_C") (pintype "passive"))
      (node (ref "D59") (pin "C") (pinfunction "C_C") (pintype "passive"))
      (node (ref "U101") (pin "26") (pinfunction "RB5/AN13/CPS5/P2B/CCP3/P3A/T1G/COM1_26") (pintype "bidirectional"))
    )
    (net (code "16") (name "/COL10") (class "Default")
      (node (ref "D100") (pin "C") (pinfunction "C_C") (pintype "passive"))
      (node (ref "D110") (pin "C") (pinfunction "C_C") (pintype "passive"))
      (node (ref "D60") (pin "C") (pinfunction "C_C") (pintype "passive"))
      (node (ref "D70") (pin "C") (pinfunction "C_C") (pintype "passive"))
      (node (ref "D80") (pin "C") (pinfunction "C_C") (pintype "passive"))
      (node (ref "D90") (pin "C") (pinfunction "C_C") (pintype "passive"))
      (node (ref "U1") (pin "15") (pinfunction "RC4/SDI/SDA/T1G/SEG11_15") (pintype "bidirectional"))
    )
    (net (code "17") (name "/COL11") (class "Default")
      (node (ref "D101") (pin "C") (pinfunction "C_C") (pintype "passive"))
      (node (ref "D111") (pin "C") (pinfunction "C_C") (pintype "passive"))
      (node (ref "D61") (pin "C") (pinfunction "C_C") (pintype "passive"))
      (node (ref "D71") (pin "C") (pinfunction "C_C") (pintype "passive"))
      (node (ref "D81") (pin "C") (pinfunction "C_C") (pintype "passive"))
      (node (ref "D91") (pin "C") (pinfunction "C_C") (pintype "passive"))
      (node (ref "U1") (pin "16") (pinfunction "RC5/SDO/SEG10_16") (pintype "bidirectional"))
    )
    (net (code "18") (name "/COL12") (class "Default")
      (node (ref "D102") (pin "C") (pinfunction "C_C") (pintype "passive"))
      (node (ref "D112") (pin "C") (pinfunction "C_C") (pintype "passive"))
      (node (ref "D62") (pin "C") (pinfunction "C_C") (pintype "passive"))
      (node (ref "D72") (pin "C") (pinfunction "C_C") (pintype "passive"))
      (node (ref "D82") (pin "C") (pinfunction "C_C") (pintype "passive"))
      (node (ref "D92") (pin "C") (pinfunction "C_C") (pintype "passive"))
      (node (ref "U1") (pin "17") (pinfunction "RC6/TX/CK/CCP3/P3A/SEG9_17") (pintype "bidirectional"))
    )
    (net (code "19") (name "/COL13") (class "Default")
      (node (ref "D103") (pin "C") (pinfunction "C_C") (pintype "passive"))
      (node (ref "D113") (pin "C") (pinfunction "C_C") (pintype "passive"))
      (node (ref "D63") (pin "C") (pinfunction "C_C") (pintype "passive"))
      (node (ref "D73") (pin "C") (pinfunction "C_C") (pintype "passive"))
      (node (ref "D83") (pin "C") (pinfunction "C_C") (pintype "passive"))
      (node (ref "D93") (pin "C") (pinfunction "C_C") (pintype "passive"))
      (node (ref "U1") (pin "18") (pinfunction "RC7/RX/DT/P3B/SEG8_18") (pintype "bidirectional"))
    )
    (net (code "20") (name "/COL14") (class "Default")
      (node (ref "D104") (pin "C") (pinfunction "C_C") (pintype "passive"))
      (node (ref "D114") (pin "C") (pinfunction "C_C") (pintype "passive"))
      (node (ref "D64") (pin "C") (pinfunction "C_C") (pintype "passive"))
      (node (ref "D74") (pin "C") (pinfunction "C_C") (pintype "passive"))
      (node (ref "D84") (pin "C") (pinfunction "C_C") (pintype "passive"))
      (node (ref "D94") (pin "C") (pinfunction "C_C") (pintype "passive"))
      (node (ref "U1") (pin "21") (pinfunction "RB0/AN12/CPS0/CCP4/SRI/INT/SEG0_21") (pintype "bidirectional"))
    )
    (net (code "21") (name "/COL15") (class "Default")
      (node (ref "D105") (pin "C") (pinfunction "C_C") (pintype "passive"))
      (node (ref "D115") (pin "C") (pinfunction "C_C") (pintype "passive"))
      (node (ref "D65") (pin "C") (pinfunction "C_C") (pintype "passive"))
      (node (ref "D75") (pin "C") (pinfunction "C_C") (pintype "passive"))
      (node (ref "D85") (pin "C") (pinfunction "C_C") (pintype "passive"))
      (node (ref "D95") (pin "C") (pinfunction "C_C") (pintype "passive"))
      (node (ref "U1") (pin "22") (pinfunction "RB1/AN10/C12IN3-/CPS1/P1C/VLCD1_22") (pintype "bidirectional"))
    )
    (net (code "22") (name "/COL16") (class "Default")
      (node (ref "D106") (pin "C") (pinfunction "C_C") (pintype "passive"))
      (node (ref "D116") (pin "C") (pinfunction "C_C") (pintype "passive"))
      (node (ref "D66") (pin "C") (pinfunction "C_C") (pintype "passive"))
      (node (ref "D76") (pin "C") (pinfunction "C_C") (pintype "passive"))
      (node (ref "D86") (pin "C") (pinfunction "C_C") (pintype "passive"))
      (node (ref "D96") (pin "C") (pinfunction "C_C") (pintype "passive"))
      (node (ref "U1") (pin "23") (pinfunction "RB2/AN8/CPS2/P1B/VLCD2_23") (pintype "bidirectional"))
    )
    (net (code "23") (name "/COL17") (class "Default")
      (node (ref "D107") (pin "C") (pinfunction "C_C") (pintype "passive"))
      (node (ref "D117") (pin "C") (pinfunction "C_C") (pintype "passive"))
      (node (ref "D67") (pin "C") (pinfunction "C_C") (pintype "passive"))
      (node (ref "D77") (pin "C") (pinfunction "C_C") (pintype "passive"))
      (node (ref "D87") (pin "C") (pinfunction "C_C") (pintype "passive"))
      (node (ref "D97") (pin "C") (pinfunction "C_C") (pintype "passive"))
      (node (ref "U1") (pin "24") (pinfunction "RB3/AN9/C12IN2-/CPS3/CCP2/P2A/VLCD3_24") (pintype "bidirectional"))
    )
    (net (code "24") (name "/COL18") (class "Default")
      (node (ref "D108") (pin "C") (pinfunction "C_C") (pintype "passive"))
      (node (ref "D118") (pin "C") (pinfunction "C_C") (pintype "passive"))
      (node (ref "D68") (pin "C") (pinfunction "C_C") (pintype "passive"))
      (node (ref "D78") (pin "C") (pinfunction "C_C") (pintype "passive"))
      (node (ref "D88") (pin "C") (pinfunction "C_C") (pintype "passive"))
      (node (ref "D98") (pin "C") (pinfunction "C_C") (pintype "passive"))
      (node (ref "U1") (pin "25") (pinfunction "RB4/AN11/CPS4/P1D/COM0_25") (pintype "bidirectional"))
    )
    (net (code "25") (name "/COL19") (class "Default")
      (node (ref "D109") (pin "C") (pinfunction "C_C") (pintype "passive"))
      (node (ref "D119") (pin "C") (pinfunction "C_C") (pintype "passive"))
      (node (ref "D69") (pin "C") (pinfunction "C_C") (pintype "passive"))
      (node (ref "D79") (pin "C") (pinfunction "C_C") (pintype "passive"))
      (node (ref "D89") (pin "C") (pinfunction "C_C") (pintype "passive"))
      (node (ref "D99") (pin "C") (pinfunction "C_C") (pintype "passive"))
      (node (ref "U1") (pin "26") (pinfunction "RB5/AN13/CPS5/P2B/CCP3/P3A/T1G/COM1_26") (pintype "bidirectional"))
    )
    (net (code "26") (name "/CS0") (class "Default")
      (node (ref "J701") (pin "2") (pinfunction "CS_2") (pintype "bidirectional"))
      (node (ref "U401") (pin "31") (pinfunction "(SSEL0/PWM2/EINT2)P0.7_31") (pintype "bidirectional"))
    )
    (net (code "27") (name "/H_RST") (class "Default")
      (node (ref "J101") (pin "10") (pinfunction "10_10") (pintype "passive"))
      (node (ref "SJ12") (pin "3") (pinfunction "3_3") (pintype "passive"))
      (node (ref "SJ2") (pin "3") (pinfunction "3_3") (pintype "passive"))
      (node (ref "U401") (pin "38") (pinfunction "(DSR1/MAT1.0/AD1.3)P0.12_38") (pintype "bidirectional"))
    )
    (net (code "28") (name "/H_TICK") (class "Default")
      (node (ref "J101") (pin "11") (pinfunction "11_11") (pintype "passive"))
      (node (ref "SJ1") (pin "3") (pinfunction "3_3") (pintype "passive"))
      (node (ref "SJ21") (pin "3") (pinfunction "3_3") (pintype "passive"))
      (node (ref "U401") (pin "39") (pinfunction "(DTR1/MAT1.1/AD1.4)P0.13_39") (pintype "bidirectional"))
    )
    (net (code "29") (name "/ISPCLK") (class "Default")
      (node (ref "SJ11") (pin "2") (pinfunction "2_2") (pintype "passive"))
      (node (ref "U101") (pin "27") (pinfunction "RB6/ICSPCLK/ICDCLK/SEG14_27") (pintype "bidirectional"))
    )
    (net (code "30") (name "/ISPCLK2") (class "Default")
      (node (ref "SJ22") (pin "2") (pinfunction "2_2") (pintype "passive"))
      (node (ref "U1") (pin "27") (pinfunction "RB6/ICSPCLK/ICDCLK/SEG14_27") (pintype "bidirectional"))
    )
    (net (code "31") (name "/ISPCLKC") (class "Default")
      (node (ref "J101") (pin "2") (pinfunction "2_2") (pintype "passive"))
      (node (ref "SJ11") (pin "3") (pinfunction "3_3") (pintype "passive"))
      (node (ref "SJ22") (pin "3") (pinfunction "3_3") (pintype "passive"))
    )
    (net (code "32") (name "/ISPDAT") (class "Default")
      (node (ref "SJ10") (pin "2") (pinfunction "2_2") (pintype "passive"))
      (node (ref "U101") (pin "28") (pinfunction "RB7/ICSPDAT/ICDDAT/SEG13_28") (pintype "bidirectional"))
    )
    (net (code "33") (name "/ISPDAT2") (class "Default")
      (node (ref "SJ20") (pin "2") (pinfunction "2_2") (pintype "passive"))
      (node (ref "U1") (pin "28") (pinfunction "RB7/ICSPDAT/ICDDAT/SEG13_28") (pintype "bidirectional"))
    )
    (net (code "34") (name "/ISPDATC") (class "Default")
      (node (ref "J101") (pin "1") (pinfunction "1_1") (pintype "passive"))
      (node (ref "SJ10") (pin "3") (pinfunction "3_3") (pintype "passive"))
      (node (ref "SJ20") (pin "3") (pinfunction "3_3") (pintype "passive"))
    )
    (net (code "35") (name "/MCLR") (class "Default")
      (node (ref "SJ9") (pin "2") (pinfunction "2_2") (pintype "passive"))
      (node (ref "U101") (pin "1") (pinfunction "VPP/~{MCLR}/RE3_1") (pintype "input"))
    )
    (net (code "36") (name "/MCLR2") (class "Default")
      (node (ref "SJ19") (pin "2") (pinfunction "2_2") (pintype "passive"))
      (node (ref "U1") (pin "1") (pinfunction "VPP/~{MCLR}/RE3_1") (pintype "input"))
    )
    (net (code "37") (name "/MCLRC") (class "Default")
      (node (ref "J101") (pin "3") (pinfunction "3_3") (pintype "passive"))
      (node (ref "SJ19") (pin "3") (pinfunction "3_3") (pintype "passive"))
      (node (ref "SJ9") (pin "3") (pinfunction "3_3") (pintype "passive"))
    )
    (net (code "38") (name "/MISO0") (class "Default")
      (node (ref "J701") (pin "7") (pinfunction "DO_7") (pintype "bidirectional"))
      (node (ref "U401") (pin "29") (pinfunction "(MISO0/MAT0.1/A0.7)P0.5_29") (pintype "bidirectional"))
    )
    (net (code "39") (name "/MOSI0") (class "Default")
      (node (ref "J701") (pin "3") (pinfunction "DI_3") (pintype "bidirectional"))
      (node (ref "U401") (pin "30") (pinfunction "(MOSI0/CAP0.2/AD1.0)P0.6_30") (pintype "bidirectional"))
    )
    (net (code "40") (name "/M_RST") (class "Default")
      (node (ref "J101") (pin "8") (pinfunction "8_8") (pintype "passive"))
      (node (ref "SJ14") (pin "3") (pinfunction "3_3") (pintype "passive"))
      (node (ref "SJ4") (pin "3") (pinfunction "3_3") (pintype "passive"))
      (node (ref "U401") (pin "35") (pinfunction "(RTS1/CAP1.0/AD1.2)P0.10_35") (pintype "bidirectional"))
    )
    (net (code "41") (name "/M_TICK") (class "Default")
      (node (ref "J101") (pin "9") (pinfunction "9_9") (pintype "passive"))
      (node (ref "SJ13") (pin "3") (pinfunction "3_3") (pintype "passive"))
      (node (ref "SJ3") (pin "3") (pinfunction "3_3") (pintype "passive"))
      (node (ref "U401") (pin "37") (pinfunction "(CTS1/CAP1.1/SCL1)P0.11_37") (pintype "bidirectional"))
    )
    (net (code "42") (name "/PPS") (class "Default")
      (node (ref "J403") (pin "6") (pinfunction "1PPS_6") (pintype "bidirectional"))
      (node (ref "U401") (pin "46") (pinfunction "(EINT0/MAT0.2/CAP0.2)P0.16_46") (pintype "bidirectional"))
    )
    (net (code "43") (name "/RESET") (class "Default")
      (node (ref "J1") (pin "3") (pinfunction "3_3") (pintype "passive"))
      (node (ref "J401") (pin "3") (pinfunction "3_3") (pintype "passive"))
      (node (ref "R400") (pin "8") (pinfunction "2_8") (pintype "passive"))
      (node (ref "U401") (pin "57") (pinfunction "RESET_57") (pintype "input"))
    )
    (net (code "44") (name "/ROW00") (class "Default")
      (node (ref "D00") (pin "A") (pinfunction "A_A") (pintype "passive"))
      (node (ref "D01") (pin "A") (pinfunction "A_A") (pintype "passive"))
      (node (ref "D02") (pin "A") (pinfunction "A_A") (pintype "passive"))
      (node (ref "D03") (pin "A") (pinfunction "A_A") (pintype "passive"))
      (node (ref "D04") (pin "A") (pinfunction "A_A") (pintype "passive"))
      (node (ref "D05") (pin "A") (pinfunction "A_A") (pintype "passive"))
      (node (ref "D06") (pin "A") (pinfunction "A_A") (pintype "passive"))
      (node (ref "D07") (pin "A") (pinfunction "A_A") (pintype "passive"))
      (node (ref "D08") (pin "A") (pinfunction "A_A") (pintype "passive"))
      (node (ref "D09") (pin "A") (pinfunction "A_A") (pintype "passive"))
      (node (ref "R101") (pin "8") (pinfunction "2_8") (pintype "passive"))
    )
    (net (code "45") (name "/ROW00C") (class "Default")
      (node (ref "R101") (pin "1") (pinfunction "1_1") (pintype "passive"))
      (node (ref "U101") (pin "14") (pinfunction "SEG6/SCL/SCK/RC3_14") (pintype "bidirectional"))
    )
    (net (code "46") (name "/ROW10") (class "Default")
      (node (ref "D10") (pin "A") (pinfunction "A_A") (pintype "passive"))
      (node (ref "D11") (pin "A") (pinfunction "A_A") (pintype "passive"))
      (node (ref "D12") (pin "A") (pinfunction "A_A") (pintype "passive"))
      (node (ref "D13") (pin "A") (pinfunction "A_A") (pintype "passive"))
      (node (ref "D14") (pin "A") (pinfunction "A_A") (pintype "passive"))
      (node (ref "D15") (pin "A") (pinfunction "A_A") (pintype "passive"))
      (node (ref "D16") (pin "A") (pinfunction "A_A") (pintype "passive"))
      (node (ref "D17") (pin "A") (pinfunction "A_A") (pintype "passive"))
      (node (ref "D18") (pin "A") (pinfunction "A_A") (pintype "passive"))
      (node (ref "D19") (pin "A") (pinfunction "A_A") (pintype "passive"))
      (node (ref "R101") (pin "7") (pinfunction "2_7") (pintype "passive"))
    )
    (net (code "47") (name "/ROW10C") (class "Default")
      (node (ref "R101") (pin "2") (pinfunction "1_2") (pintype "passive"))
      (node (ref "U101") (pin "13") (pinfunction "SEG3/P1A/CCP1/RC2_13") (pintype "bidirectional"))
    )
    (net (code "48") (name "/ROW20") (class "Default")
      (node (ref "D20") (pin "A") (pinfunction "A_A") (pintype "passive"))
      (node (ref "D21") (pin "A") (pinfunction "A_A") (pintype "passive"))
      (node (ref "D22") (pin "A") (pinfunction "A_A") (pintype "passive"))
      (node (ref "D23") (pin "A") (pinfunction "A_A") (pintype "passive"))
      (node (ref "D24") (pin "A") (pinfunction "A_A") (pintype "passive"))
      (node (ref "D25") (pin "A") (pinfunction "A_A") (pintype "passive"))
      (node (ref "D26") (pin "A") (pinfunction "A_A") (pintype "passive"))
      (node (ref "D27") (pin "A") (pinfunction "A_A") (pintype "passive"))
      (node (ref "D28") (pin "A") (pinfunction "A_A") (pintype "passive"))
      (node (ref "D29") (pin "A") (pinfunction "A_A") (pintype "passive"))
      (node (ref "R101") (pin "6") (pinfunction "2_6") (pintype "passive"))
    )
    (net (code "49") (name "/ROW20C") (class "Default")
      (node (ref "R101") (pin "3") (pinfunction "1_3") (pintype "passive"))
      (node (ref "U101") (pin "12") (pinfunction "P2A/CCP2/T1OSI/RC1_12") (pintype "bidirectional"))
    )
    (net (code "50") (name "/ROW30") (class "Default")
      (node (ref "D30") (pin "A") (pinfunction "A_A") (pintype "passive"))
      (node (ref "D31") (pin "A") (pinfunction "A_A") (pintype "passive"))
      (node (ref "D32") (pin "A") (pinfunction "A_A") (pintype "passive"))
      (node (ref "D33") (pin "A") (pinfunction "A_A") (pintype "passive"))
      (node (ref "D34") (pin "A") (pinfunction "A_A") (pintype "passive"))
      (node (ref "D35") (pin "A") (pinfunction "A_A") (pintype "passive"))
      (node (ref "D36") (pin "A") (pinfunction "A_A") (pintype "passive"))
      (node (ref "D37") (pin "A") (pinfunction "A_A") (pintype "passive"))
      (node (ref "D38") (pin "A") (pinfunction "A_A") (pintype "passive"))
      (node (ref "D39") (pin "A") (pinfunction "A_A") (pintype "passive"))
      (node (ref "R102") (pin "7") (pinfunction "2_7") (pintype "passive"))
    )
    (net (code "51") (name "/ROW30C") (class "Default")
      (node (ref "R102") (pin "2") (pinfunction "1_2") (pintype "passive"))
      (node (ref "U101") (pin "9") (pinfunction "SEG2/CLKIN/OSC1/RA7_9") (pintype "bidirectional"))
    )
    (net (code "52") (name "/ROW40") (class "Default")
      (node (ref "D40") (pin "A") (pinfunction "A_A") (pintype "passive"))
      (node (ref "D41") (pin "A") (pinfunction "A_A") (pintype "passive"))
      (node (ref "D42") (pin "A") (pinfunction "A_A") (pintype "passive"))
      (node (ref "D43") (pin "A") (pinfunction "A_A") (pintype "passive"))
      (node (ref "D44") (pin "A") (pinfunction "A_A") (pintype "passive"))
      (node (ref "D45") (pin "A") (pinfunction "A_A") (pintype "passive"))
      (node (ref "D46") (pin "A") (pinfunction "A_A") (pintype "passive"))
      (node (ref "D47") (pin "A") (pinfunction "A_A") (pintype "passive"))
      (node (ref "D48") (pin "A") (pinfunction "A_A") (pintype "passive"))
      (node (ref "D49") (pin "A") (pinfunction "A_A") (pintype "passive"))
      (node (ref "R102") (pin "8") (pinfunction "2_8") (pintype "passive"))
    )
    (net (code "53") (name "/ROW40C") (class "Default")
      (node (ref "R102") (pin "1") (pinfunction "1_1") (pintype "passive"))
      (node (ref "U101") (pin "10") (pinfunction "SEG1/VCAP/CLKOUT/OSC2/RA6_10") (pintype "bidirectional"))
    )
    (net (code "54") (name "/ROW50") (class "Default")
      (node (ref "D50") (pin "A") (pinfunction "A_A") (pintype "passive"))
      (node (ref "D51") (pin "A") (pinfunction "A_A") (pintype "passive"))
      (node (ref "D52") (pin "A") (pinfunction "A_A") (pintype "passive"))
      (node (ref "D53") (pin "A") (pinfunction "A_A") (pintype "passive"))
      (node (ref "D54") (pin "A") (pinfunction "A_A") (pintype "passive"))
      (node (ref "D55") (pin "A") (pinfunction "A_A") (pintype "passive"))
      (node (ref "D56") (pin "A") (pinfunction "A_A") (pintype "passive"))
      (node (ref "D57") (pin "A") (pinfunction "A_A") (pintype "passive"))
      (node (ref "D58") (pin "A") (pinfunction "A_A") (pintype "passive"))
      (node (ref "D59") (pin "A") (pinfunction "A_A") (pintype "passive"))
      (node (ref "R101") (pin "5") (pinfunction "2_5") (pintype "passive"))
    )
    (net (code "55") (name "/ROW50C") (class "Default")
      (node (ref "R101") (pin "4") (pinfunction "1_4") (pintype "passive"))
      (node (ref "U101") (pin "11") (pinfunction "P2B/T1CKI/T1OSO/RC0_11") (pintype "bidirectional"))
    )
    (net (code "56") (name "/ROW200") (class "Default")
      (node (ref "D60") (pin "A") (pinfunction "A_A") (pintype "passive"))
      (node (ref "D61") (pin "A") (pinfunction "A_A") (pintype "passive"))
      (node (ref "D62") (pin "A") (pinfunction "A_A") (pintype "passive"))
      (node (ref "D63") (pin "A") (pinfunction "A_A") (pintype "passive"))
      (node (ref "D64") (pin "A") (pinfunction "A_A") (pintype "passive"))
      (node (ref "D65") (pin "A") (pinfunction "A_A") (pintype "passive"))
      (node (ref "D66") (pin "A") (pinfunction "A_A") (pintype "passive"))
      (node (ref "D67") (pin "A") (pinfunction "A_A") (pintype "passive"))
      (node (ref "D68") (pin "A") (pinfunction "A_A") (pintype "passive"))
      (node (ref "D69") (pin "A") (pinfunction "A_A") (pintype "passive"))
      (node (ref "R201") (pin "8") (pinfunction "2_8") (pintype "passive"))
    )
    (net (code "57") (name "/ROW200C") (class "Default")
      (node (ref "R201") (pin "1") (pinfunction "1_1") (pintype "passive"))
      (node (ref "U1") (pin "14") (pinfunction "SEG6/SCL/SCK/RC3_14") (pintype "bidirectional"))
    )
    (net (code "58") (name "/ROW210") (class "Default")
      (node (ref "D70") (pin "A") (pinfunction "A_A") (pintype "passive"))
      (node (ref "D71") (pin "A") (pinfunction "A_A") (pintype "passive"))
      (node (ref "D72") (pin "A") (pinfunction "A_A") (pintype "passive"))
      (node (ref "D73") (pin "A") (pinfunction "A_A") (pintype "passive"))
      (node (ref "D74") (pin "A") (pinfunction "A_A") (pintype "passive"))
      (node (ref "D75") (pin "A") (pinfunction "A_A") (pintype "passive"))
      (node (ref "D76") (pin "A") (pinfunction "A_A") (pintype "passive"))
      (node (ref "D77") (pin "A") (pinfunction "A_A") (pintype "passive"))
      (node (ref "D78") (pin "A") (pinfunction "A_A") (pintype "passive"))
      (node (ref "D79") (pin "A") (pinfunction "A_A") (pintype "passive"))
      (node (ref "R201") (pin "7") (pinfunction "2_7") (pintype "passive"))
    )
    (net (code "59") (name "/ROW210C") (class "Default")
      (node (ref "R201") (pin "2") (pinfunction "1_2") (pintype "passive"))
      (node (ref "U1") (pin "13") (pinfunction "SEG3/P1A/CCP1/RC2_13") (pintype "bidirectional"))
    )
    (net (code "60") (name "/ROW220") (class "Default")
      (node (ref "D80") (pin "A") (pinfunction "A_A") (pintype "passive"))
      (node (ref "D81") (pin "A") (pinfunction "A_A") (pintype "passive"))
      (node (ref "D82") (pin "A") (pinfunction "A_A") (pintype "passive"))
      (node (ref "D83") (pin "A") (pinfunction "A_A") (pintype "passive"))
      (node (ref "D84") (pin "A") (pinfunction "A_A") (pintype "passive"))
      (node (ref "D85") (pin "A") (pinfunction "A_A") (pintype "passive"))
      (node (ref "D86") (pin "A") (pinfunction "A_A") (pintype "passive"))
      (node (ref "D87") (pin "A") (pinfunction "A_A") (pintype "passive"))
      (node (ref "D88") (pin "A") (pinfunction "A_A") (pintype "passive"))
      (node (ref "D89") (pin "A") (pinfunction "A_A") (pintype "passive"))
      (node (ref "R201") (pin "6") (pinfunction "2_6") (pintype "passive"))
    )
    (net (code "61") (name "/ROW220C") (class "Default")
      (node (ref "R201") (pin "3") (pinfunction "1_3") (pintype "passive"))
      (node (ref "U1") (pin "12") (pinfunction "P2A/CCP2/T1OSI/RC1_12") (pintype "bidirectional"))
    )
    (net (code "62") (name "/ROW230") (class "Default")
      (node (ref "D90") (pin "A") (pinfunction "A_A") (pintype "passive"))
      (node (ref "D91") (pin "A") (pinfunction "A_A") (pintype "passive"))
      (node (ref "D92") (pin "A") (pinfunction "A_A") (pintype "passive"))
      (node (ref "D93") (pin "A") (pinfunction "A_A") (pintype "passive"))
      (node (ref "D94") (pin "A") (pinfunction "A_A") (pintype "passive"))
      (node (ref "D95") (pin "A") (pinfunction "A_A") (pintype "passive"))
      (node (ref "D96") (pin "A") (pinfunction "A_A") (pintype "passive"))
      (node (ref "D97") (pin "A") (pinfunction "A_A") (pintype "passive"))
      (node (ref "D98") (pin "A") (pinfunction "A_A") (pintype "passive"))
      (node (ref "D99") (pin "A") (pinfunction "A_A") (pintype "passive"))
      (node (ref "R202") (pin "7") (pinfunction "2_7") (pintype "passive"))
    )
    (net (code "63") (name "/ROW230C") (class "Default")
      (node (ref "R202") (pin "2") (pinfunction "1_2") (pintype "passive"))
      (node (ref "U1") (pin "9") (pinfunction "SEG2/CLKIN/OSC1/RA7_9") (pintype "bidirectional"))
    )
    (net (code "64") (name "/ROW240") (class "Default")
      (node (ref "D100") (pin "A") (pinfunction "A_A") (pintype "passive"))
      (node (ref "D101") (pin "A") (pinfunction "A_A") (pintype "passive"))
      (node (ref "D102") (pin "A") (pinfunction "A_A") (pintype "passive"))
      (node (ref "D103") (pin "A") (pinfunction "A_A") (pintype "passive"))
      (node (ref "D104") (pin "A") (pinfunction "A_A") (pintype "passive"))
      (node (ref "D105") (pin "A") (pinfunction "A_A") (pintype "passive"))
      (node (ref "D106") (pin "A") (pinfunction "A_A") (pintype "passive"))
      (node (ref "D107") (pin "A") (pinfunction "A_A") (pintype "passive"))
      (node (ref "D108") (pin "A") (pinfunction "A_A") (pintype "passive"))
      (node (ref "D109") (pin "A") (pinfunction "A_A") (pintype "passive"))
      (node (ref "R202") (pin "8") (pinfunction "2_8") (pintype "passive"))
    )
    (net (code "65") (name "/ROW240C") (class "Default")
      (node (ref "R202") (pin "1") (pinfunction "1_1") (pintype "passive"))
      (node (ref "U1") (pin "10") (pinfunction "SEG1/VCAP/CLKOUT/OSC2/RA6_10") (pintype "bidirectional"))
    )
    (net (code "66") (name "/ROW250") (class "Default")
      (node (ref "D110") (pin "A") (pinfunction "A_A") (pintype "passive"))
      (node (ref "D111") (pin "A") (pinfunction "A_A") (pintype "passive"))
      (node (ref "D112") (pin "A") (pinfunction "A_A") (pintype "passive"))
      (node (ref "D113") (pin "A") (pinfunction "A_A") (pintype "passive"))
      (node (ref "D114") (pin "A") (pinfunction "A_A") (pintype "passive"))
      (node (ref "D115") (pin "A") (pinfunction "A_A") (pintype "passive"))
      (node (ref "D116") (pin "A") (pinfunction "A_A") (pintype "passive"))
      (node (ref "D117") (pin "A") (pinfunction "A_A") (pintype "passive"))
      (node (ref "D118") (pin "A") (pinfunction "A_A") (pintype "passive"))
      (node (ref "D119") (pin "A") (pinfunction "A_A") (pintype "passive"))
      (node (ref "R201") (pin "5") (pinfunction "2_5") (pintype "passive"))
    )
    (net (code "67") (name "/ROW250C") (class "Default")
      (node (ref "R201") (pin "4") (pinfunction "1_4") (pintype "passive"))
      (node (ref "U1") (pin "11") (pinfunction "P2B/T1CKI/T1OSO/RC0_11") (pintype "bidirectional"))
    )
    (net (code "68") (name "/RX0") (class "Default")
      (node (ref "J1") (pin "2") (pinfunction "2_2") (pintype "passive"))
      (node (ref "J401") (pin "2") (pinfunction "2_2") (pintype "passive"))
      (node (ref "J403") (pin "4") (pinfunction "TX_4") (pintype "bidirectional"))
      (node (ref "U401") (pin "21") (pinfunction "(RXD0/PWM3/EINT0)P0.1_21") (pintype "bidirectional"))
    )
    (net (code "69") (name "/RX1") (class "Default")
      (node (ref "J1") (pin "11") (pinfunction "11_11") (pintype "passive"))
      (node (ref "J401") (pin "11") (pinfunction "11_11") (pintype "passive"))
      (node (ref "U401") (pin "34") (pinfunction "(RXD1/PWM6/EINT3)P0.9_34") (pintype "bidirectional"))
    )
    (net (code "70") (name "/SCK0") (class "Default")
      (node (ref "J701") (pin "5") (pinfunction "SCK_5") (pintype "bidirectional"))
      (node (ref "U401") (pin "27") (pinfunction "(SCK0/CAP0.1/AD0.6)P0.4_27") (pintype "bidirectional"))
    )
    (net (code "71") (name "/S_RST") (class "Default")
      (node (ref "J101") (pin "6") (pinfunction "6_6") (pintype "passive"))
      (node (ref "SJ16") (pin "3") (pinfunction "3_3") (pintype "passive"))
      (node (ref "SJ6") (pin "3") (pinfunction "3_3") (pintype "passive"))
      (node (ref "U401") (pin "47") (pinfunction "(CAP1.2/SCK1/MAT1.2)P0.17_47") (pintype "bidirectional"))
    )
    (net (code "72") (name "/S_TICK") (class "Default")
      (node (ref "J101") (pin "7") (pinfunction "7_7") (pintype "passive"))
      (node (ref "SJ15") (pin "3") (pinfunction "3_3") (pintype "passive"))
      (node (ref "SJ5") (pin "3") (pinfunction "3_3") (pintype "passive"))
      (node (ref "U401") (pin "53") (pinfunction "(CAP1.3/MISO1/MAT1.3)P0.18_53") (pintype "bidirectional"))
    )
    (net (code "73") (name "/TX0") (class "Default")
      (node (ref "J1") (pin "1") (pinfunction "1_1") (pintype "passive"))
      (node (ref "J401") (pin "1") (pinfunction "1_1") (pintype "passive"))
      (node (ref "J403") (pin "3") (pinfunction "RX_3") (pintype "bidirectional"))
      (node (ref "U401") (pin "19") (pinfunction "(TXD0/PWM1)P0.0_19") (pintype "bidirectional"))
    )
    (net (code "74") (name "/TX1") (class "Default")
      (node (ref "J1") (pin "10") (pinfunction "10_10") (pintype "passive"))
      (node (ref "J401") (pin "10") (pinfunction "10_10") (pintype "passive"))
      (node (ref "U401") (pin "33") (pinfunction "(TXD1/PWM4/A1.1)P0.8_33") (pintype "bidirectional"))
    )
    (net (code "75") (name "/T_RST") (class "Default")
      (node (ref "J101") (pin "4") (pinfunction "4_4") (pintype "passive"))
      (node (ref "SJ18") (pin "3") (pinfunction "3_3") (pintype "passive"))
      (node (ref "SJ8") (pin "3") (pinfunction "3_3") (pintype "passive"))
    )
    (net (code "76") (name "/T_TICK") (class "Default")
      (node (ref "J101") (pin "5") (pinfunction "5_5") (pintype "passive"))
      (node (ref "SJ17") (pin "3") (pinfunction "3_3") (pintype "passive"))
      (node (ref "SJ7") (pin "3") (pinfunction "3_3") (pintype "passive"))
    )
    (net (code "77") (name "/USBCONN_D+") (class "Default")
      (node (ref "J1") (pin "5") (pinfunction "5_5") (pintype "passive"))
      (node (ref "J401") (pin "5") (pinfunction "5_5") (pintype "passive"))
      (node (ref "R030") (pin "2") (pinfunction "2_2") (pintype "passive"))
      (node (ref "R031") (pin "2") (pinfunction "2_2") (pintype "passive"))
    )
    (net (code "78") (name "/USBCONN_D-") (class "Default")
      (node (ref "J1") (pin "7") (pinfunction "7_7") (pintype "passive"))
      (node (ref "J401") (pin "7") (pinfunction "7_7") (pintype "passive"))
      (node (ref "R020") (pin "2") (pinfunction "2_2") (pintype "passive"))
    )
    (net (code "79") (name "/USBD+") (class "Default")
      (node (ref "C030") (pin "1") (pinfunction "1_1") (pintype "passive"))
      (node (ref "R030") (pin "1") (pinfunction "1_1") (pintype "passive"))
      (node (ref "U401") (pin "10") (pinfunction "(AD0.5)P0.26_10") (pintype "bidirectional"))
    )
    (net (code "80") (name "/USBD-") (class "Default")
      (node (ref "C020") (pin "1") (pinfunction "1_1") (pintype "passive"))
      (node (ref "R020") (pin "1") (pinfunction "1_1") (pintype "passive"))
      (node (ref "U401") (pin "11") (pinfunction "(AD0.0/CAP0.1/MAT0.1)P0.27_11") (pintype "bidirectional"))
    )
    (net (code "81") (name "/USB_ON") (class "Default")
      (node (ref "R400") (pin "3") (pinfunction "1_3") (pintype "passive"))
      (node (ref "U401") (pin "58") (pinfunction "P0.23_58") (pintype "bidirectional"))
    )
    (net (code "82") (name "/USB_SOFTCONNECT") (class "Default")
      (node (ref "Q002") (pin "1") (pinfunction "G_1") (pintype "passive"))
      (node (ref "R400") (pin "5") (pinfunction "2_5") (pintype "passive"))
      (node (ref "U401") (pin "17") (pinfunction "P0.31_17") (pintype "output"))
    )
    (net (code "83") (name "/VBUS") (class "Default")
      (node (ref "C010") (pin "1") (pinfunction "1_1") (pintype "passive"))
      (node (ref "C120") (pin "2") (pinfunction "2_2") (pintype "passive"))
      (node (ref "C201") (pin "1") (pinfunction "1_1") (pintype "passive"))
      (node (ref "C220") (pin "2") (pinfunction "2_2") (pintype "passive"))
      (node (ref "J1") (pin "8") (pinfunction "8_8") (pintype "passive"))
      (node (ref "J401") (pin "8") (pinfunction "8_8") (pintype "passive"))
      (node (ref "J403") (pin "2") (pinfunction "VCC_2") (pintype "bidirectional"))
      (node (ref "R011") (pin "2") (pinfunction "2_2") (pintype "passive"))
      (node (ref "R400") (pin "6") (pinfunction "2_6") (pintype "passive"))
      (node (ref "SJ19") (pin "1") (pinfunction "1_1") (pintype "passive"))
      (node (ref "SJ9") (pin "1") (pinfunction "1_1") (pintype "passive"))
      (node (ref "U1") (pin "20") (pinfunction "VDD_20") (pintype "power_in"))
      (node (ref "U101") (pin "20") (pinfunction "VDD_20") (pintype "power_in"))
      (node (ref "U201") (pin "1") (pinfunction "EN_1") (pintype "input"))
      (node (ref "U201") (pin "2") (pinfunction "IN_2") (pintype "input"))
    )
    (net (code "84") (name "/XTAL1") (class "Default")
      (node (ref "C462") (pin "2") (pinfunction "2_2") (pintype "passive"))
      (node (ref "U401") (pin "62") (pinfunction "XTAL1_62") (pintype "input"))
      (node (ref "Y1") (pin "3") (pinfunction "2_3") (pintype "passive"))
    )
    (net (code "85") (name "/XTAL2") (class "Default")
      (node (ref "C461") (pin "2") (pinfunction "2_2") (pintype "passive"))
      (node (ref "U401") (pin "61") (pinfunction "XTAL2_61") (pintype "output"))
      (node (ref "Y1") (pin "1") (pinfunction "1_1") (pintype "passive"))
    )
    (net (code "86") (name "GND") (class "Default")
      (node (ref "C010") (pin "2") (pinfunction "2_2") (pintype "passive"))
      (node (ref "C020") (pin "2") (pinfunction "2_2") (pintype "passive"))
      (node (ref "C030") (pin "2") (pinfunction "2_2") (pintype "passive"))
      (node (ref "C120") (pin "1") (pinfunction "1_1") (pintype "passive"))
      (node (ref "C201") (pin "2") (pinfunction "2_2") (pintype "passive"))
      (node (ref "C202") (pin "C") (pinfunction "-_C") (pintype "passive"))
      (node (ref "C203") (pin "2") (pinfunction "2_2") (pintype "passive"))
      (node (ref "C220") (pin "1") (pinfunction "1_1") (pintype "passive"))
      (node (ref "C407") (pin "2") (pinfunction "2_2") (pintype "passive"))
      (node (ref "C423") (pin "2") (pinfunction "2_2") (pintype "passive"))
      (node (ref "C443") (pin "2") (pinfunction "2_2") (pintype "passive"))
      (node (ref "C451") (pin "2") (pinfunction "2_2") (pintype "passive"))
      (node (ref "C461") (pin "1") (pinfunction "1_1") (pintype "passive"))
      (node (ref "C462") (pin "1") (pinfunction "1_1") (pintype "passive"))
      (node (ref "C701") (pin "2") (pinfunction "2_2") (pintype "passive"))
      (node (ref "J1") (pin "9") (pinfunction "9_9") (pintype "passive"))
      (node (ref "J401") (pin "9") (pinfunction "9_9") (pintype "passive"))
      (node (ref "J403") (pin "1") (pinfunction "GND1_1") (pintype "bidirectional"))
      (node (ref "J403") (pin "5") (pinfunction "GND2_5") (pintype "bidirectional"))
      (node (ref "J701") (pin "6") (pinfunction "GND_6") (pintype "bidirectional"))
      (node (ref "J701") (pin "CD2") (pinfunction "SHIELD_CD2") (pintype "bidirectional"))
      (node (ref "J701") (pin "GND1") (pinfunction "SHIELD_GND1") (pintype "bidirectional"))
      (node (ref "R011") (pin "1") (pinfunction "1_1") (pintype "passive"))
      (node (ref "SJ1") (pin "1") (pinfunction "1_1") (pintype "passive"))
      (node (ref "SJ10") (pin "1") (pinfunction "1_1") (pintype "passive"))
      (node (ref "SJ11") (pin "1") (pinfunction "1_1") (pintype "passive"))
      (node (ref "SJ12") (pin "1") (pinfunction "1_1") (pintype "passive"))
      (node (ref "SJ13") (pin "1") (pinfunction "1_1") (pintype "passive"))
      (node (ref "SJ14") (pin "1") (pinfunction "1_1") (pintype "passive"))
      (node (ref "SJ15") (pin "1") (pinfunction "1_1") (pintype "passive"))
      (node (ref "SJ16") (pin "1") (pinfunction "1_1") (pintype "passive"))
      (node (ref "SJ17") (pin "1") (pinfunction "1_1") (pintype "passive"))
      (node (ref "SJ18") (pin "1") (pinfunction "1_1") (pintype "passive"))
      (node (ref "SJ2") (pin "1") (pinfunction "1_1") (pintype "passive"))
      (node (ref "SJ20") (pin "1") (pinfunction "1_1") (pintype "passive"))
      (node (ref "SJ21") (pin "1") (pinfunction "1_1") (pintype "passive"))
      (node (ref "SJ22") (pin "1") (pinfunction "1_1") (pintype "passive"))
      (node (ref "SJ3") (pin "1") (pinfunction "1_1") (pintype "passive"))
      (node (ref "SJ4") (pin "1") (pinfunction "1_1") (pintype "passive"))
      (node (ref "SJ5") (pin "1") (pinfunction "1_1") (pintype "passive"))
      (node (ref "SJ6") (pin "1") (pinfunction "1_1") (pintype "passive"))
      (node (ref "SJ7") (pin "1") (pinfunction "1_1") (pintype "passive"))
      (node (ref "SJ8") (pin "1") (pinfunction "1_1") (pintype "passive"))
      (node (ref "U1") (pin "19") (pinfunction "VSS_19") (pintype "power_in"))
      (node (ref "U1") (pin "8") (pinfunction "VSS_8") (pintype "power_in"))
      (node (ref "U101") (pin "19") (pinfunction "VSS_19") (pintype "power_in"))
      (node (ref "U101") (pin "8") (pinfunction "VSS_8") (pintype "power_in"))
      (node (ref "U201") (pin "5") (pinfunction "GND_5") (pintype "power_in"))
      (node (ref "U201") (pin "6") (pinfunction "GND_6") (pintype "power_in"))
      (node (ref "U201") (pin "7") (pinfunction "GND_7") (pintype "power_in"))
      (node (ref "U201") (pin "8") (pinfunction "GND_8") (pintype "power_in"))
      (node (ref "U401") (pin "18") (pinfunction "VSS_18") (pintype "power_in"))
      (node (ref "U401") (pin "25") (pinfunction "VSS_25") (pintype "power_in"))
      (node (ref "U401") (pin "42") (pinfunction "VSS_42") (pintype "power_in"))
      (node (ref "U401") (pin "50") (pinfunction "VSS_50") (pintype "power_in"))
      (node (ref "U401") (pin "59") (pinfunction "VSSA_59") (pintype "power_in"))
      (node (ref "U401") (pin "6") (pinfunction "VSS_6") (pintype "power_in"))
      (node (ref "Y1") (pin "2") (pinfunction "1_2") (pintype "bidirectional"))
      (node (ref "Y1") (pin "4") (pinfunction "1_4") (pintype "bidirectional"))
    )
    (net (code "87") (name "Net-(Q002-D)") (class "Default")
      (node (ref "Q002") (pin "3") (pinfunction "D_3") (pintype "passive"))
      (node (ref "R031") (pin "1") (pinfunction "1_1") (pintype "passive"))
    )
    (net (code "88") (name "Net-(U201A-BYP)") (class "Default")
      (node (ref "C203") (pin "1") (pinfunction "1_1") (pintype "passive"))
      (node (ref "U201") (pin "4") (pinfunction "BYP_4") (pintype "passive"))
    )
    (net (code "89") (name "VCC") (class "Default")
      (node (ref "C202") (pin "A") (pinfunction "+_A") (pintype "passive"))
      (node (ref "C407") (pin "1") (pinfunction "1_1") (pintype "passive"))
      (node (ref "C423") (pin "1") (pinfunction "1_1") (pintype "passive"))
      (node (ref "C443") (pin "1") (pinfunction "1_1") (pintype "passive"))
      (node (ref "C451") (pin "1") (pinfunction "1_1") (pintype "passive"))
      (node (ref "C701") (pin "1") (pinfunction "1_1") (pintype "passive"))
      (node (ref "J1") (pin "6") (pinfunction "6_6") (pintype "passive"))
      (node (ref "J401") (pin "6") (pinfunction "6_6") (pintype "passive"))
      (node (ref "J701") (pin "4") (pinfunction "VCC_4") (pintype "bidirectional"))
      (node (ref "Q002") (pin "2") (pinfunction "S_2") (pintype "passive"))
      (node (ref "R400") (pin "1") (pinfunction "1_1") (pintype "passive"))
      (node (ref "R400") (pin "2") (pinfunction "1_2") (pintype "passive"))
      (node (ref "R400") (pin "4") (pinfunction "1_4") (pintype "passive"))
      (node (ref "U201") (pin "3") (pinfunction "OUT_3") (pintype "output"))
      (node (ref "U401") (pin "23") (pinfunction "VDD3-1_23") (pintype "power_in"))
      (node (ref "U401") (pin "3") (pinfunction "RTXC1_3") (pintype "input"))
      (node (ref "U401") (pin "43") (pinfunction "VDD3-2_43") (pintype "power_in"))
      (node (ref "U401") (pin "49") (pinfunction "VBAT_49") (pintype "power_in"))
      (node (ref "U401") (pin "51") (pinfunction "VDD3-3_51") (pintype "power_in"))
      (node (ref "U401") (pin "63") (pinfunction "VREF_63") (pintype "input"))
      (node (ref "U401") (pin "7") (pinfunction "VDDA3_7") (pintype "power_in"))
    )
    (net (code "90") (name "unconnected-(J701-NC-Pad1)") (class "Default")
      (node (ref "J701") (pin "1") (pinfunction "NC_1") (pintype "bidirectional"))
    )
    (net (code "91") (name "unconnected-(J701-RSV-Pad8)") (class "Default")
      (node (ref "J701") (pin "8") (pinfunction "RSV_8") (pintype "bidirectional"))
    )
    (net (code "92") (name "unconnected-(J701-SHIELD-PadCD1)") (class "Default")
      (node (ref "J701") (pin "CD1") (pinfunction "SHIELD_CD1") (pintype "bidirectional"))
    )
    (net (code "93") (name "unconnected-(J701-SHIELD-PadGND3)") (class "Default")
      (node (ref "J701") (pin "GND3") (pinfunction "SHIELD_GND3") (pintype "bidirectional"))
    )
    (net (code "94") (name "unconnected-(U1-COM2{slash}DACOUT{slash}VREF-{slash}C2IN+{slash}AN2{slash}RA2-Pad4)") (class "Default")
      (node (ref "U1") (pin "4") (pinfunction "COM2/DACOUT/VREF-/C2IN+/AN2/RA2_4") (pintype "bidirectional"))
    )
    (net (code "95") (name "unconnected-(U1-SEG7{slash}C12IN1-{slash}AN1{slash}RA1-Pad3)") (class "Default")
      (node (ref "U1") (pin "3") (pinfunction "SEG7/C12IN1-/AN1/RA1_3") (pintype "bidirectional"))
    )
    (net (code "96") (name "unconnected-(U1-SEG12{slash}VCAP{slash}SS{slash}SRNQ{slash}C2OUT{slash}C12IN0-{slash}AN0{slash}RA0-Pad2)") (class "Default")
      (node (ref "U1") (pin "2") (pinfunction "SEG12/VCAP/SS/SRNQ/C2OUT/C12IN0-/AN0/RA0_2") (pintype "bidirectional"))
    )
    (net (code "97") (name "unconnected-(U1-SEG15{slash}COM3{slash}VREF+{slash}C1IN+{slash}AN3{slash}RA3-Pad5)") (class "Default")
      (node (ref "U1") (pin "5") (pinfunction "SEG15/COM3/VREF+/C1IN+/AN3/RA3_5") (pintype "bidirectional"))
    )
    (net (code "98") (name "unconnected-(U101-COM2{slash}DACOUT{slash}VREF-{slash}C2IN+{slash}AN2{slash}RA2-Pad4)") (class "Default")
      (node (ref "U101") (pin "4") (pinfunction "COM2/DACOUT/VREF-/C2IN+/AN2/RA2_4") (pintype "bidirectional"))
    )
    (net (code "99") (name "unconnected-(U101-SEG7{slash}C12IN1-{slash}AN1{slash}RA1-Pad3)") (class "Default")
      (node (ref "U101") (pin "3") (pinfunction "SEG7/C12IN1-/AN1/RA1_3") (pintype "bidirectional"))
    )
    (net (code "100") (name "unconnected-(U101-SEG12{slash}VCAP{slash}SS{slash}SRNQ{slash}C2OUT{slash}C12IN0-{slash}AN0{slash}RA0-Pad2)") (class "Default")
      (node (ref "U101") (pin "2") (pinfunction "SEG12/VCAP/SS/SRNQ/C2OUT/C12IN0-/AN0/RA0_2") (pintype "bidirectional"))
    )
    (net (code "101") (name "unconnected-(U101-SEG15{slash}COM3{slash}VREF+{slash}C1IN+{slash}AN3{slash}RA3-Pad5)") (class "Default")
      (node (ref "U101") (pin "5") (pinfunction "SEG15/COM3/VREF+/C1IN+/AN3/RA3_5") (pintype "bidirectional"))
    )
    (net (code "102") (name "unconnected-(U401-(AD0.1{slash}CAP0.2{slash}MAT0.2)P0.28-Pad13)") (class "Default")
      (node (ref "U401") (pin "13") (pinfunction "(AD0.1/CAP0.2/MAT0.2)P0.28_13") (pintype "bidirectional"))
    )
    (net (code "103") (name "unconnected-(U401-(AD0.2{slash}CAP0.3{slash}MAT0.3)P0.29-Pad14)") (class "Default")
      (node (ref "U401") (pin "14") (pinfunction "(AD0.2/CAP0.3/MAT0.3)P0.29_14") (pintype "bidirectional"))
    )
    (net (code "104") (name "unconnected-(U401-(AD0.3{slash}EINT3{slash}CAP0.0)P0.30-Pad15)") (class "Default")
      (node (ref "U401") (pin "15") (pinfunction "(AD0.3/EINT3/CAP0.0)P0.30_15") (pintype "bidirectional"))
    )
    (net (code "105") (name "unconnected-(U401-(AD0.4{slash}AOUT)P0.25-Pad9)") (class "Default")
      (node (ref "U401") (pin "9") (pinfunction "(AD0.4/AOUT)P0.25_9") (pintype "bidirectional"))
    )
    (net (code "106") (name "unconnected-(U401-(AD1.7{slash}CAP0.0{slash}MAT0.0)P0.22-Pad2)") (class "Default")
      (node (ref "U401") (pin "2") (pinfunction "(AD1.7/CAP0.0/MAT0.0)P0.22_2") (pintype "bidirectional"))
    )
    (net (code "107") (name "unconnected-(U401-(MAT1.2{slash}MOSI1{slash}CAP1.2)P0.19-Pad54)") (class "Default")
      (node (ref "U401") (pin "54") (pinfunction "(MAT1.2/MOSI1/CAP1.2)P0.19_54") (pintype "bidirectional"))
    )
    (net (code "108") (name "unconnected-(U401-(MAT1.3{slash}SSEL1{slash}EINT3)P0.20-Pad55)") (class "Default")
      (node (ref "U401") (pin "55") (pinfunction "(MAT1.3/SSEL1/EINT3)P0.20_55") (pintype "bidirectional"))
    )
    (net (code "109") (name "unconnected-(U401-(PWM5{slash}AD1.6{slash}CAP1.3)P0.21-Pad1)") (class "Default")
      (node (ref "U401") (pin "1") (pinfunction "(PWM5/AD1.6/CAP1.3)P0.21_1") (pintype "bidirectional"))
    )
    (net (code "110") (name "unconnected-(U401-(RI1{slash}EINT2{slash}AD1.5)P0.15-Pad45)") (class "Default")
      (node (ref "U401") (pin "45") (pinfunction "(RI1/EINT2/AD1.5)P0.15_45") (pintype "bidirectional"))
    )
    (net (code "111") (name "unconnected-(U401-(SCL0{slash}CAP0.0)P0.2-Pad22)") (class "Default")
      (node (ref "U401") (pin "22") (pinfunction "(SCL0/CAP0.0)P0.2_22") (pintype "bidirectional"))
    )
    (net (code "112") (name "unconnected-(U401-(SDA0{slash}MAT0.0{slash}EINT1)P0.3-Pad26)") (class "Default")
      (node (ref "U401") (pin "26") (pinfunction "(SDA0/MAT0.0/EINT1)P0.3_26") (pintype "bidirectional"))
    )
    (net (code "113") (name "unconnected-(U401-P1.16(TRACEPKT0)-Pad16)") (class "Default")
      (node (ref "U401") (pin "16") (pinfunction "P1.16(TRACEPKT0)_16") (pintype "bidirectional"))
    )
    (net (code "114") (name "unconnected-(U401-P1.17(TRACEPKT1)-Pad12)") (class "Default")
      (node (ref "U401") (pin "12") (pinfunction "P1.17(TRACEPKT1)_12") (pintype "bidirectional"))
    )
    (net (code "115") (name "unconnected-(U401-P1.18(TRACEPKT2)-Pad8)") (class "Default")
      (node (ref "U401") (pin "8") (pinfunction "P1.18(TRACEPKT2)_8") (pintype "bidirectional"))
    )
    (net (code "116") (name "unconnected-(U401-P1.19(TRACEPKT3)-Pad4)") (class "Default")
      (node (ref "U401") (pin "4") (pinfunction "P1.19(TRACEPKT3)_4") (pintype "bidirectional"))
    )
    (net (code "117") (name "unconnected-(U401-P1.20(TRACESYNC)-Pad48)") (class "Default")
      (node (ref "U401") (pin "48") (pinfunction "P1.20(TRACESYNC)_48") (pintype "bidirectional"))
    )
    (net (code "118") (name "unconnected-(U401-P1.21(PIPESTAT0)-Pad44)") (class "Default")
      (node (ref "U401") (pin "44") (pinfunction "P1.21(PIPESTAT0)_44") (pintype "bidirectional"))
    )
    (net (code "119") (name "unconnected-(U401-P1.22(PIPESTAT1)-Pad40)") (class "Default")
      (node (ref "U401") (pin "40") (pinfunction "P1.22(PIPESTAT1)_40") (pintype "bidirectional"))
    )
    (net (code "120") (name "unconnected-(U401-P1.23(PIPESTAT2)-Pad36)") (class "Default")
      (node (ref "U401") (pin "36") (pinfunction "P1.23(PIPESTAT2)_36") (pintype "bidirectional"))
    )
    (net (code "121") (name "unconnected-(U401-P1.24(TRACECLK)-Pad32)") (class "Default")
      (node (ref "U401") (pin "32") (pinfunction "P1.24(TRACECLK)_32") (pintype "bidirectional"))
    )
    (net (code "122") (name "unconnected-(U401-P1.25(EXTIN0)-Pad28)") (class "Default")
      (node (ref "U401") (pin "28") (pinfunction "P1.25(EXTIN0)_28") (pintype "bidirectional"))
    )
    (net (code "123") (name "unconnected-(U401-P1.26(RTCK)-Pad24)") (class "Default")
      (node (ref "U401") (pin "24") (pinfunction "P1.26(RTCK)_24") (pintype "bidirectional"))
    )
    (net (code "124") (name "unconnected-(U401-P1.27(TDO)-Pad64)") (class "Default")
      (node (ref "U401") (pin "64") (pinfunction "P1.27(TDO)_64") (pintype "bidirectional"))
    )
    (net (code "125") (name "unconnected-(U401-P1.28(TDI)-Pad60)") (class "Default")
      (node (ref "U401") (pin "60") (pinfunction "P1.28(TDI)_60") (pintype "bidirectional"))
    )
    (net (code "126") (name "unconnected-(U401-P1.29(TCK)-Pad56)") (class "Default")
      (node (ref "U401") (pin "56") (pinfunction "P1.29(TCK)_56") (pintype "bidirectional"))
    )
    (net (code "127") (name "unconnected-(U401-P1.30(TMS)-Pad52)") (class "Default")
      (node (ref "U401") (pin "52") (pinfunction "P1.30(TMS)_52") (pintype "bidirectional"))
    )
    (net (code "128") (name "unconnected-(U401-P1.31({slash}TRST)-Pad20)") (class "Default")
      (node (ref "U401") (pin "20") (pinfunction "P1.31(/TRST)_20") (pintype "bidirectional"))
    )
    (net (code "129") (name "unconnected-(U401-RTXC2-Pad5)") (class "Default")
      (node (ref "U401") (pin "5") (pinfunction "RTXC2_5") (pintype "output"))
    )
  )
)
